# A-14732-40023-REPRODUCTION.net
KiCad netlist of a schematic drawn in EAGLE
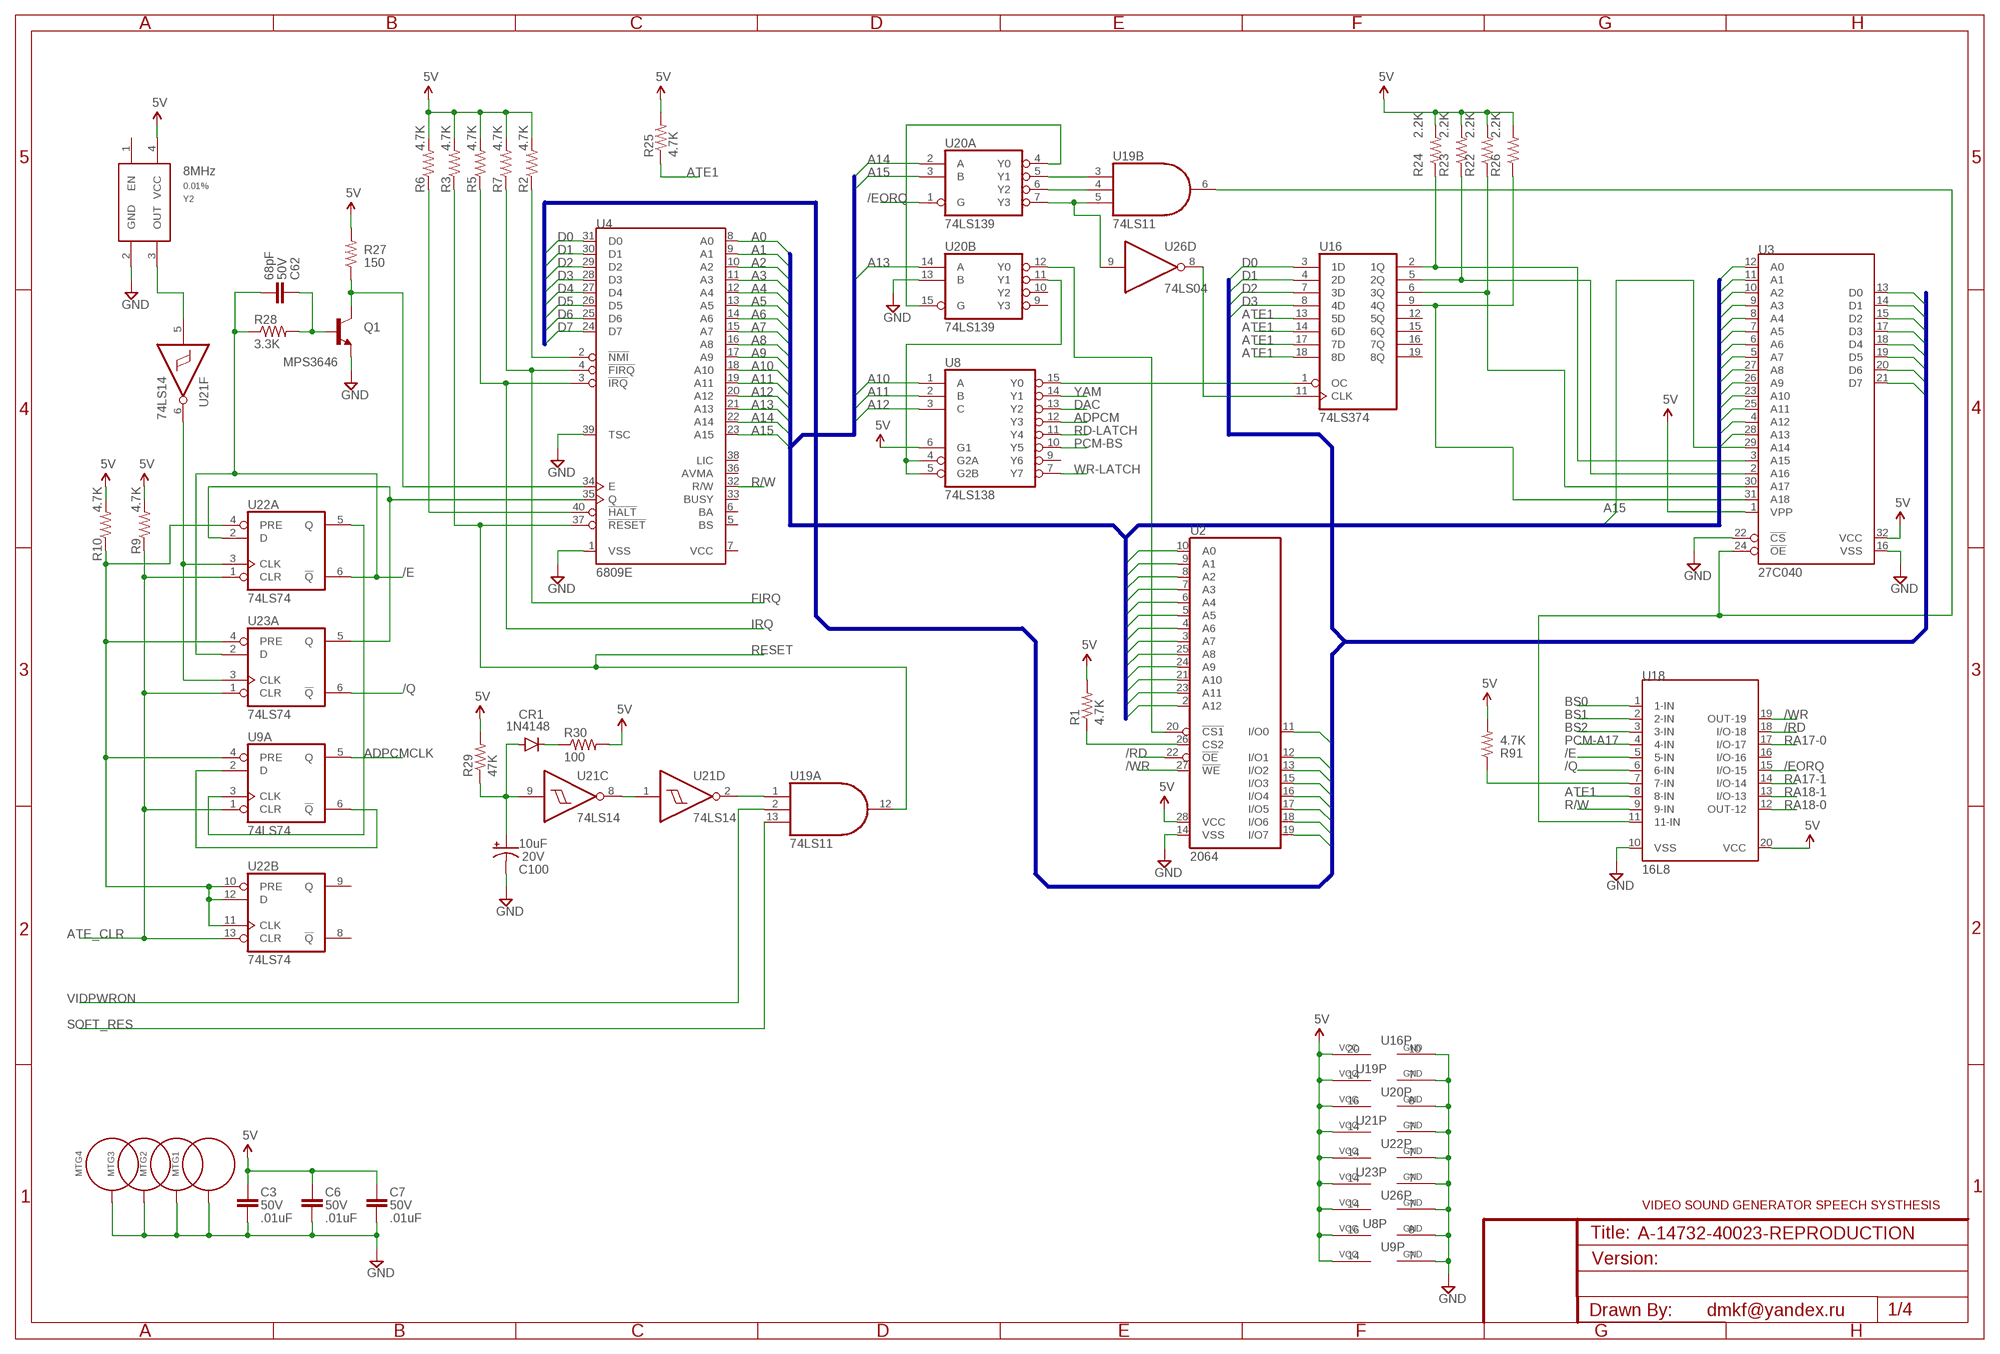
[diagram p0: schematic, sheet 1]
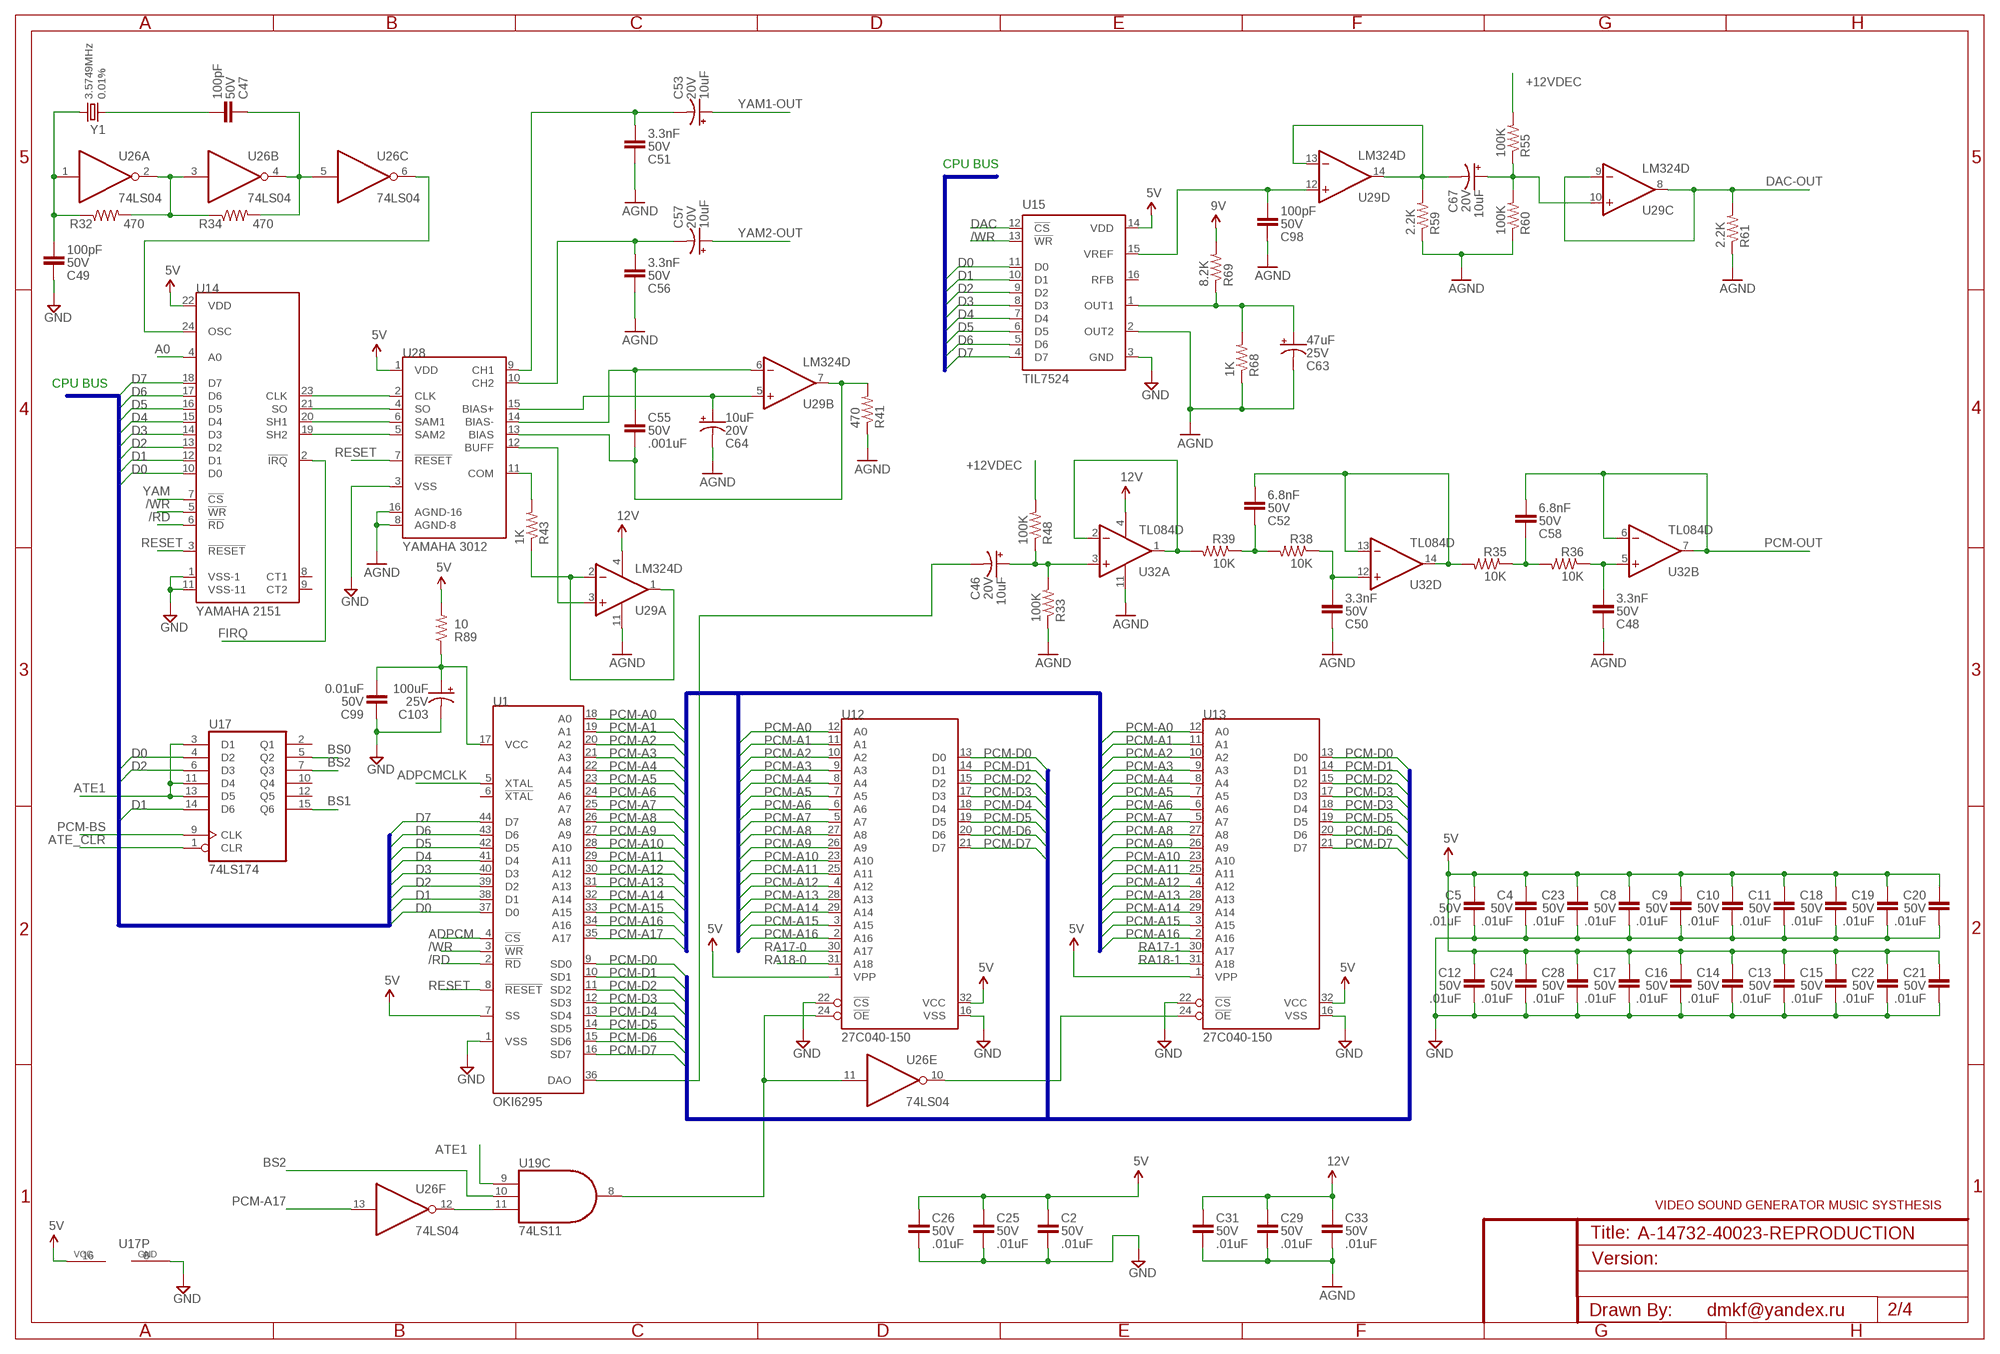
[diagram p1: schematic, sheet 2]
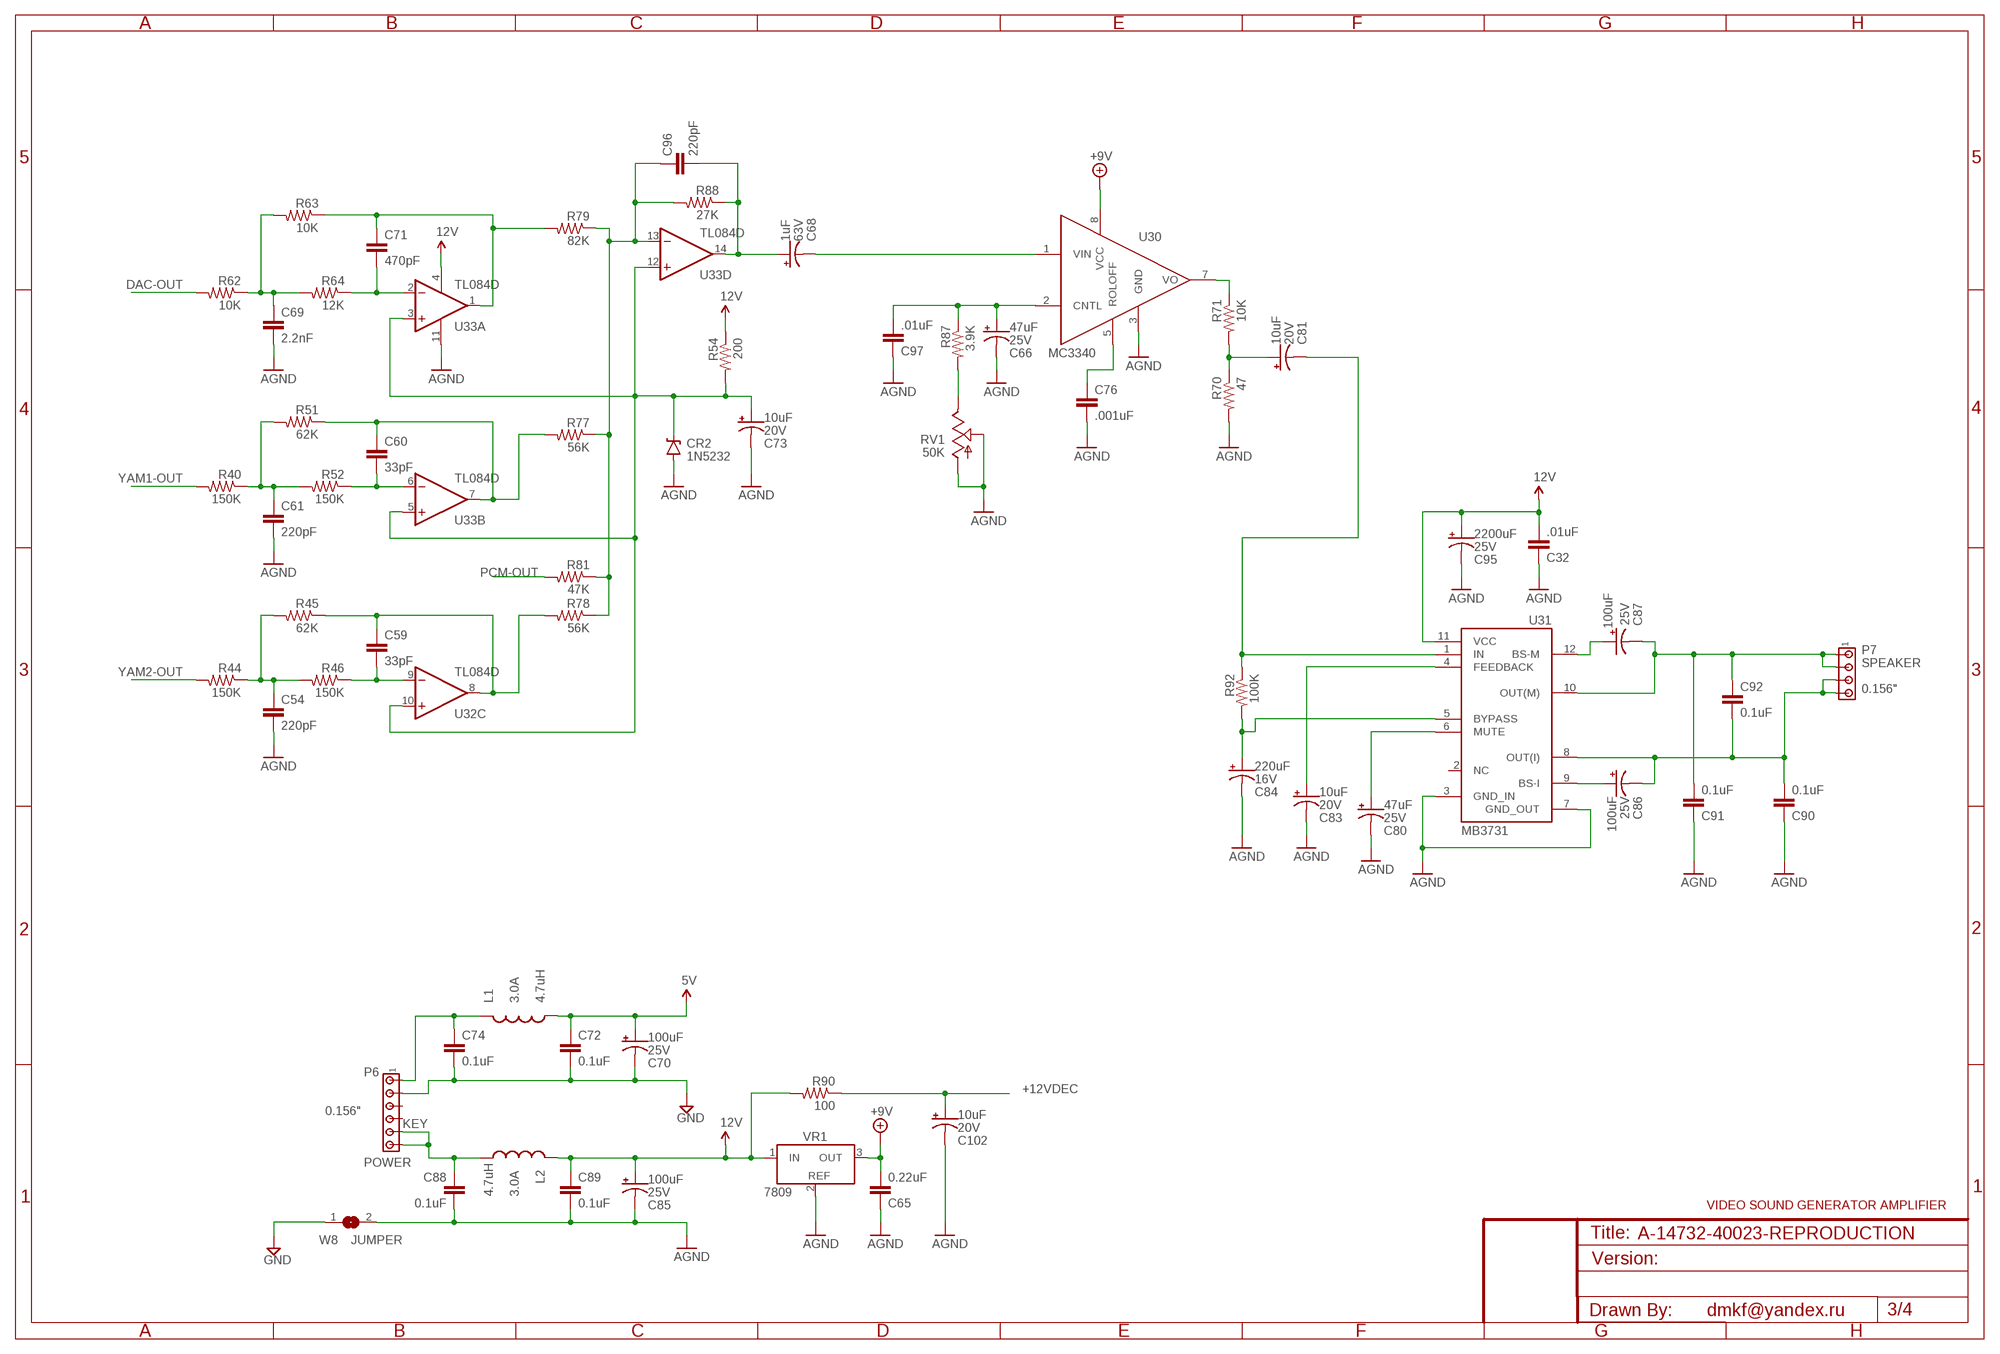
[diagram p2: schematic, sheet 3]
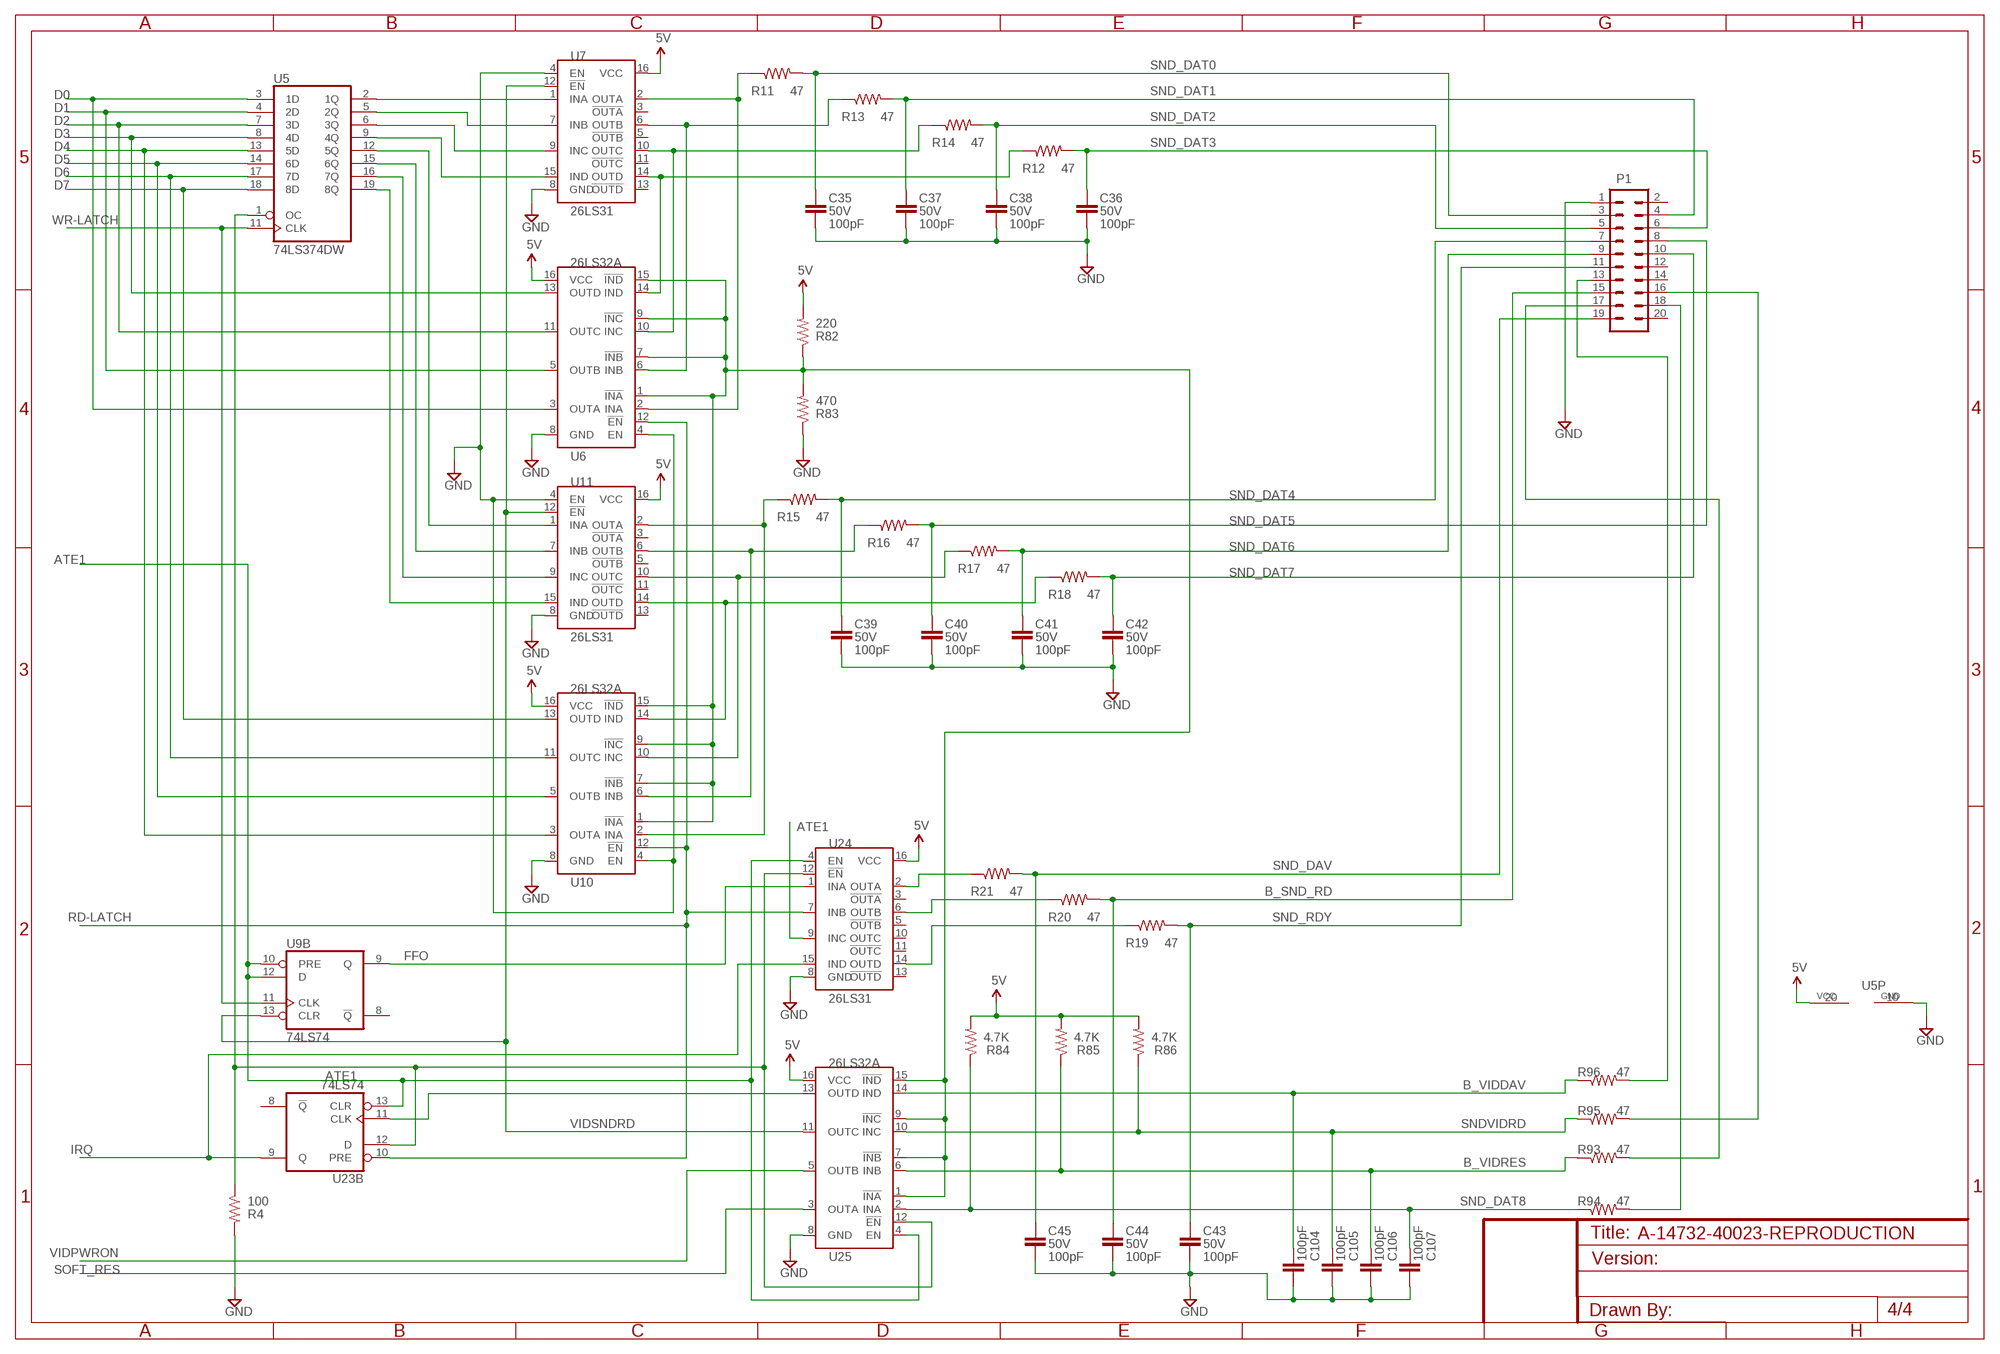
[diagram p3: schematic, sheet 4]

(export (version "E")
  (design (tool "Eeschema 10.0.6"))
  (components
    (comp (ref "C2")
      (value ".01uF")
      (footprint "eagle-import:0805")
      (fields (field (name "VOLTAGE") "50V"))
      (libsource (lib "eagle-import") (part "CAP0805"))
    )
    (comp (ref "C4")
      (value ".01uF")
      (footprint "eagle-import:0805")
      (fields (field (name "VOLTAGE") "50V"))
      (libsource (lib "eagle-import") (part "CAP0805"))
    )
    (comp (ref "C5")
      (value ".01uF")
      (footprint "eagle-import:0805")
      (fields (field (name "VOLTAGE") "50V"))
      (libsource (lib "eagle-import") (part "CAP0805"))
    )
    (comp (ref "C8")
      (value ".01uF")
      (footprint "eagle-import:0805")
      (fields (field (name "VOLTAGE") "50V"))
      (libsource (lib "eagle-import") (part "CAP0805"))
    )
    (comp (ref "C9")
      (value ".01uF")
      (footprint "eagle-import:0805")
      (fields (field (name "VOLTAGE") "50V"))
      (libsource (lib "eagle-import") (part "CAP0805"))
    )
    (comp (ref "C10")
      (value ".01uF")
      (footprint "eagle-import:0805")
      (fields (field (name "VOLTAGE") "50V"))
      (libsource (lib "eagle-import") (part "CAP0805"))
    )
    (comp (ref "C11")
      (value ".01uF")
      (footprint "eagle-import:0805")
      (fields (field (name "VOLTAGE") "50V"))
      (libsource (lib "eagle-import") (part "CAP0805"))
    )
    (comp (ref "C12")
      (value ".01uF")
      (footprint "eagle-import:0805")
      (fields (field (name "VOLTAGE") "50V"))
      (libsource (lib "eagle-import") (part "CAP0805"))
    )
    (comp (ref "C13")
      (value ".01uF")
      (footprint "eagle-import:0805")
      (fields (field (name "VOLTAGE") "50V"))
      (libsource (lib "eagle-import") (part "CAP0805"))
    )
    (comp (ref "C14")
      (value ".01uF")
      (footprint "eagle-import:0805")
      (fields (field (name "VOLTAGE") "50V"))
      (libsource (lib "eagle-import") (part "CAP0805"))
    )
    (comp (ref "C15")
      (value ".01uF")
      (footprint "eagle-import:0805")
      (fields (field (name "VOLTAGE") "50V"))
      (libsource (lib "eagle-import") (part "CAP0805"))
    )
    (comp (ref "C16")
      (value ".01uF")
      (footprint "eagle-import:0805")
      (fields (field (name "VOLTAGE") "50V"))
      (libsource (lib "eagle-import") (part "CAP0805"))
    )
    (comp (ref "C17")
      (value ".01uF")
      (footprint "eagle-import:0805")
      (fields (field (name "VOLTAGE") "50V"))
      (libsource (lib "eagle-import") (part "CAP0805"))
    )
    (comp (ref "C18")
      (value ".01uF")
      (footprint "eagle-import:0805")
      (fields (field (name "VOLTAGE") "50V"))
      (libsource (lib "eagle-import") (part "CAP0805"))
    )
    (comp (ref "C19")
      (value ".01uF")
      (footprint "eagle-import:0805")
      (fields (field (name "VOLTAGE") "50V"))
      (libsource (lib "eagle-import") (part "CAP0805"))
    )
    (comp (ref "C20")
      (value ".01uF")
      (footprint "eagle-import:0805")
      (fields (field (name "VOLTAGE") "50V"))
      (libsource (lib "eagle-import") (part "CAP0805"))
    )
    (comp (ref "C21")
      (value ".01uF")
      (footprint "eagle-import:0805")
      (fields (field (name "VOLTAGE") "50V"))
      (libsource (lib "eagle-import") (part "CAP0805"))
    )
    (comp (ref "C22")
      (value ".01uF")
      (footprint "eagle-import:0805")
      (fields (field (name "VOLTAGE") "50V"))
      (libsource (lib "eagle-import") (part "CAP0805"))
    )
    (comp (ref "C23")
      (value ".01uF")
      (footprint "eagle-import:0805")
      (fields (field (name "VOLTAGE") "50V"))
      (libsource (lib "eagle-import") (part "CAP0805"))
    )
    (comp (ref "C24")
      (value ".01uF")
      (footprint "eagle-import:0805")
      (fields (field (name "VOLTAGE") "50V"))
      (libsource (lib "eagle-import") (part "CAP0805"))
    )
    (comp (ref "C25")
      (value ".01uF")
      (footprint "eagle-import:0805")
      (fields (field (name "VOLTAGE") "50V"))
      (libsource (lib "eagle-import") (part "CAP0805"))
    )
    (comp (ref "C26")
      (value ".01uF")
      (footprint "eagle-import:0805")
      (fields (field (name "VOLTAGE") "50V"))
      (libsource (lib "eagle-import") (part "CAP0805"))
    )
    (comp (ref "C28")
      (value ".01uF")
      (footprint "eagle-import:0805")
      (fields (field (name "VOLTAGE") "50V"))
      (libsource (lib "eagle-import") (part "CAP0805"))
    )
    (comp (ref "C29")
      (value ".01uF")
      (footprint "eagle-import:0805")
      (fields (field (name "VOLTAGE") "50V"))
      (libsource (lib "eagle-import") (part "CAP0805"))
    )
    (comp (ref "C31")
      (value ".01uF")
      (footprint "eagle-import:0805")
      (fields (field (name "VOLTAGE") "50V"))
      (libsource (lib "eagle-import") (part "CAP0805"))
    )
    (comp (ref "C33")
      (value ".01uF")
      (footprint "eagle-import:0805")
      (fields (field (name "VOLTAGE") "50V"))
      (libsource (lib "eagle-import") (part "CAP0805"))
    )
    (comp (ref "C46")
      (value "10uF")
      (footprint "eagle-import:PANASONIC_C")
      (fields (field (name "VOLTAGE") "20V"))
      (libsource (lib "eagle-import") (part "CAP_POLC"))
    )
    (comp (ref "C47")
      (value "100pF")
      (footprint "eagle-import:0805")
      (fields (field (name "VOLTAGE") "50V"))
      (libsource (lib "eagle-import") (part "CAP0805"))
    )
    (comp (ref "C48")
      (value "3.3nF")
      (footprint "eagle-import:0805")
      (fields (field (name "VOLTAGE") "50V"))
      (libsource (lib "eagle-import") (part "CAP0805"))
    )
    (comp (ref "C49")
      (value "100pF")
      (footprint "eagle-import:0805")
      (fields (field (name "VOLTAGE") "50V"))
      (libsource (lib "eagle-import") (part "CAP0805"))
    )
    (comp (ref "C50")
      (value "3.3nF")
      (footprint "eagle-import:0805")
      (fields (field (name "VOLTAGE") "50V"))
      (libsource (lib "eagle-import") (part "CAP0805"))
    )
    (comp (ref "C51")
      (value "3.3nF")
      (footprint "eagle-import:0805")
      (fields (field (name "VOLTAGE") "50V"))
      (libsource (lib "eagle-import") (part "CAP0805"))
    )
    (comp (ref "C52")
      (value "6.8nF")
      (footprint "eagle-import:0805")
      (fields (field (name "VOLTAGE") "50V"))
      (libsource (lib "eagle-import") (part "CAP0805"))
    )
    (comp (ref "C53")
      (value "10uF")
      (footprint "eagle-import:PANASONIC_C")
      (fields (field (name "VOLTAGE") "20V"))
      (libsource (lib "eagle-import") (part "CAP_POLC"))
    )
    (comp (ref "C55")
      (value ".001uF")
      (footprint "eagle-import:0805")
      (fields (field (name "VOLTAGE") "50V"))
      (libsource (lib "eagle-import") (part "CAP0805"))
    )
    (comp (ref "C56")
      (value "3.3nF")
      (footprint "eagle-import:0805")
      (fields (field (name "VOLTAGE") "50V"))
      (libsource (lib "eagle-import") (part "CAP0805"))
    )
    (comp (ref "C57")
      (value "10uF")
      (footprint "eagle-import:PANASONIC_C")
      (fields (field (name "VOLTAGE") "20V"))
      (libsource (lib "eagle-import") (part "CAP_POLC"))
    )
    (comp (ref "C58")
      (value "6.8nF")
      (footprint "eagle-import:0805")
      (fields (field (name "VOLTAGE") "50V"))
      (libsource (lib "eagle-import") (part "CAP0805"))
    )
    (comp (ref "C63")
      (value "47uF")
      (footprint "eagle-import:PANASONIC_D")
      (fields (field (name "VOLTAGE") "25V"))
      (libsource (lib "eagle-import") (part "CAP_POLD"))
    )
    (comp (ref "C64")
      (value "10uF")
      (footprint "eagle-import:PANASONIC_C")
      (fields (field (name "VOLTAGE") "20V"))
      (libsource (lib "eagle-import") (part "CAP_POLC"))
    )
    (comp (ref "C67")
      (value "10uF")
      (footprint "eagle-import:PANASONIC_C")
      (fields (field (name "VOLTAGE") "20V"))
      (libsource (lib "eagle-import") (part "CAP_POLC"))
    )
    (comp (ref "C98")
      (value "100pF")
      (footprint "eagle-import:0805")
      (fields (field (name "VOLTAGE") "50V"))
      (libsource (lib "eagle-import") (part "CAP0805"))
    )
    (comp (ref "C99")
      (value "0.01uF")
      (footprint "eagle-import:0805")
      (fields (field (name "VOLTAGE") "50V"))
      (libsource (lib "eagle-import") (part "CAP0805"))
    )
    (comp (ref "C103")
      (value "100uF")
      (footprint "eagle-import:PANASONIC_D")
      (fields (field (name "VOLTAGE") "25V"))
      (libsource (lib "eagle-import") (part "CAP_POLD"))
    )
    (comp (ref "R32")
      (value "470")
      (footprint "eagle-import:0805")
      (libsource (lib "eagle-import") (part "RESISTOR0805-RES"))
    )
    (comp (ref "R33")
      (value "100K")
      (footprint "eagle-import:0805")
      (libsource (lib "eagle-import") (part "RESISTOR0805-RES"))
    )
    (comp (ref "R34")
      (value "470")
      (footprint "eagle-import:0805")
      (libsource (lib "eagle-import") (part "RESISTOR0805-RES"))
    )
    (comp (ref "R35")
      (value "10K")
      (footprint "eagle-import:0805")
      (libsource (lib "eagle-import") (part "RESISTOR0805-RES"))
    )
    (comp (ref "R36")
      (value "10K")
      (footprint "eagle-import:0805")
      (libsource (lib "eagle-import") (part "RESISTOR0805-RES"))
    )
    (comp (ref "R38")
      (value "10K")
      (footprint "eagle-import:0805")
      (libsource (lib "eagle-import") (part "RESISTOR0805-RES"))
    )
    (comp (ref "R39")
      (value "10K")
      (footprint "eagle-import:0805")
      (libsource (lib "eagle-import") (part "RESISTOR0805-RES"))
    )
    (comp (ref "R41")
      (value "470")
      (footprint "eagle-import:0805")
      (libsource (lib "eagle-import") (part "RESISTOR0805-RES"))
    )
    (comp (ref "R43")
      (value "1K")
      (footprint "eagle-import:0805")
      (libsource (lib "eagle-import") (part "RESISTOR0805-RES"))
    )
    (comp (ref "R48")
      (value "100K")
      (footprint "eagle-import:0805")
      (libsource (lib "eagle-import") (part "RESISTOR0805-RES"))
    )
    (comp (ref "R55")
      (value "100K")
      (footprint "eagle-import:0805")
      (libsource (lib "eagle-import") (part "RESISTOR0805-RES"))
    )
    (comp (ref "R59")
      (value "2.2K")
      (footprint "eagle-import:0805")
      (libsource (lib "eagle-import") (part "RESISTOR0805-RES"))
    )
    (comp (ref "R60")
      (value "100K")
      (footprint "eagle-import:0805")
      (libsource (lib "eagle-import") (part "RESISTOR0805-RES"))
    )
    (comp (ref "R61")
      (value "2.2K")
      (footprint "eagle-import:0805")
      (libsource (lib "eagle-import") (part "RESISTOR0805-RES"))
    )
    (comp (ref "R68")
      (value "1K")
      (footprint "eagle-import:0805")
      (libsource (lib "eagle-import") (part "RESISTOR0805-RES"))
    )
    (comp (ref "R69")
      (value "8.2K")
      (footprint "eagle-import:0805")
      (libsource (lib "eagle-import") (part "RESISTOR0805-RES"))
    )
    (comp (ref "R89")
      (value "10")
      (footprint "eagle-import:1206")
      (libsource (lib "eagle-import") (part "RESISTOR1206"))
    )
    (comp (ref "U1")
      (value "OKI6295")
      (footprint "eagle-import:QFP44")
      (libsource (lib "eagle-import") (part "OKI6295"))
    )
    (comp (ref "U12")
      (value "27C040-150")
      (footprint "eagle-import:PLCC32R")
      (libsource (lib "eagle-import") (part "27C040PLCC32"))
    )
    (comp (ref "U13")
      (value "27C040-150")
      (footprint "eagle-import:PLCC32R")
      (libsource (lib "eagle-import") (part "27C040PLCC32"))
    )
    (comp (ref "U14")
      (value "YAMAHA 2151")
      (footprint "eagle-import:DIP24")
      (libsource (lib "eagle-import") (part "YM2151"))
    )
    (comp (ref "U15")
      (value "TIL7524")
      (footprint "eagle-import:SOIC16N")
      (fields (field (name "MF") "ALTERA CORPORATION") (field (name "MPN") "AD7524JRZ"))
      (libsource (lib "eagle-import") (part "AD7524RJ"))
    )
    (comp (ref "U17")
      (value "74LS174")
      (footprint "eagle-import:SO16")
      (libsource (lib "eagle-import") (part "74174DLS"))
    )
    (comp (ref "U19")
      (value "74LS11")
      (footprint "eagle-import:SO14")
      (libsource (lib "eagle-import") (part "7411DLS"))
    )
    (comp (ref "U26")
      (value "74LS04")
      (footprint "eagle-import:SO14")
      (libsource (lib "eagle-import") (part "7404DLS"))
    )
    (comp (ref "U28")
      (value "YAMAHA 3012")
      (footprint "eagle-import:DIP16N")
      (libsource (lib "eagle-import") (part "YM3012"))
    )
    (comp (ref "U29")
      (value "LM324D")
      (footprint "eagle-import:SO14")
      (libsource (lib "eagle-import") (part "LM324D"))
    )
    (comp (ref "U32")
      (value "TL084D")
      (footprint "eagle-import:SO14")
      (libsource (lib "eagle-import") (part "TL084D"))
    )
    (comp (ref "Y1")
      (value "3.5749MHz")
      (footprint "eagle-import:HC49UP")
      (fields (field (name "TOLERANCE") "0.01%"))
      (libsource (lib "eagle-import") (part "CRYSTALHC49UP"))
    )
    (comp (ref "C32")
      (value ".01uF")
      (footprint "eagle-import:0805")
      (fields (field (name "VOLTAGE") "50V"))
      (libsource (lib "eagle-import") (part "CAP0805"))
    )
    (comp (ref "C54")
      (value "220pF")
      (footprint "eagle-import:0805")
      (fields (field (name "VOLTAGE") "50V"))
      (libsource (lib "eagle-import") (part "CAP0805"))
    )
    (comp (ref "C59")
      (value "33pF")
      (footprint "eagle-import:0805")
      (fields (field (name "VOLTAGE") "50V"))
      (libsource (lib "eagle-import") (part "CAP0805"))
    )
    (comp (ref "C60")
      (value "33pF")
      (footprint "eagle-import:0805")
      (fields (field (name "VOLTAGE") "50V"))
      (libsource (lib "eagle-import") (part "CAP0805"))
    )
    (comp (ref "C61")
      (value "220pF")
      (footprint "eagle-import:0805")
      (fields (field (name "VOLTAGE") "50V"))
      (libsource (lib "eagle-import") (part "CAP0805"))
    )
    (comp (ref "C65")
      (value "0.22uF")
      (footprint "eagle-import:0805")
      (fields (field (name "VOLTAGE") "50V"))
      (libsource (lib "eagle-import") (part "CAP0805"))
    )
    (comp (ref "C66")
      (value "47uF")
      (footprint "eagle-import:PANASONIC_D")
      (fields (field (name "VOLTAGE") "25V"))
      (libsource (lib "eagle-import") (part "CAP_POLD"))
    )
    (comp (ref "C68")
      (value "1uF")
      (footprint "eagle-import:PANASONIC_C")
      (fields (field (name "VOLTAGE") "63V"))
      (libsource (lib "eagle-import") (part "CAP_POLC"))
    )
    (comp (ref "C69")
      (value "2.2nF")
      (footprint "eagle-import:0805")
      (fields (field (name "VOLTAGE") "50V"))
      (libsource (lib "eagle-import") (part "CAP0805"))
    )
    (comp (ref "C70")
      (value "100uF")
      (footprint "eagle-import:PANASONIC_D")
      (fields (field (name "VOLTAGE") "25V"))
      (libsource (lib "eagle-import") (part "CAP_POLD"))
    )
    (comp (ref "C71")
      (value "470pF")
      (footprint "eagle-import:0805")
      (fields (field (name "VOLTAGE") "50V"))
      (libsource (lib "eagle-import") (part "CAP0805"))
    )
    (comp (ref "C72")
      (value "0.1uF")
      (footprint "eagle-import:0805")
      (fields (field (name "VOLTAGE") "50V"))
      (libsource (lib "eagle-import") (part "CAP0805"))
    )
    (comp (ref "C73")
      (value "10uF")
      (footprint "eagle-import:PANASONIC_C")
      (fields (field (name "VOLTAGE") "20V"))
      (libsource (lib "eagle-import") (part "CAP_POLC"))
    )
    (comp (ref "C74")
      (value "0.1uF")
      (footprint "eagle-import:0805")
      (fields (field (name "VOLTAGE") "50V"))
      (libsource (lib "eagle-import") (part "CAP0805"))
    )
    (comp (ref "C76")
      (value ".001uF")
      (footprint "eagle-import:0805")
      (fields (field (name "VOLTAGE") "50V"))
      (libsource (lib "eagle-import") (part "CAP0805"))
    )
    (comp (ref "C80")
      (value "47uF")
      (footprint "eagle-import:PANASONIC_D")
      (fields (field (name "VOLTAGE") "25V"))
      (libsource (lib "eagle-import") (part "CAP_POLD"))
    )
    (comp (ref "C81")
      (value "10uF")
      (footprint "eagle-import:PANASONIC_C")
      (fields (field (name "VOLTAGE") "20V"))
      (libsource (lib "eagle-import") (part "CAP_POLC"))
    )
    (comp (ref "C83")
      (value "10uF")
      (footprint "eagle-import:PANASONIC_C")
      (fields (field (name "VOLTAGE") "20V"))
      (libsource (lib "eagle-import") (part "CAP_POLC"))
    )
    (comp (ref "C84")
      (value "220uF")
      (footprint "eagle-import:PANASONIC_E")
      (fields (field (name "VOLTAGE") "16V"))
      (libsource (lib "eagle-import") (part "CAP_POLE"))
    )
    (comp (ref "C85")
      (value "100uF")
      (footprint "eagle-import:PANASONIC_D")
      (fields (field (name "VOLTAGE") "25V"))
      (libsource (lib "eagle-import") (part "CAP_POLD"))
    )
    (comp (ref "C86")
      (value "100uF")
      (footprint "eagle-import:PANASONIC_D")
      (fields (field (name "VOLTAGE") "25V"))
      (libsource (lib "eagle-import") (part "CAP_POLD"))
    )
    (comp (ref "C87")
      (value "100uF")
      (footprint "eagle-import:PANASONIC_D")
      (fields (field (name "VOLTAGE") "25V"))
      (libsource (lib "eagle-import") (part "CAP_POLD"))
    )
    (comp (ref "C88")
      (value "0.1uF")
      (footprint "eagle-import:0805")
      (fields (field (name "VOLTAGE") "50V"))
      (libsource (lib "eagle-import") (part "CAP0805"))
    )
    (comp (ref "C89")
      (value "0.1uF")
      (footprint "eagle-import:0805")
      (fields (field (name "VOLTAGE") "50V"))
      (libsource (lib "eagle-import") (part "CAP0805"))
    )
    (comp (ref "C90")
      (value "0.1uF")
      (footprint "eagle-import:0805")
      (fields (field (name "VOLTAGE") "50V"))
      (libsource (lib "eagle-import") (part "CAP0805"))
    )
    (comp (ref "C91")
      (value "0.1uF")
      (footprint "eagle-import:0805")
      (fields (field (name "VOLTAGE") "50V"))
      (libsource (lib "eagle-import") (part "CAP0805"))
    )
    (comp (ref "C92")
      (value "0.1uF")
      (footprint "eagle-import:0805")
      (fields (field (name "VOLTAGE") "50V"))
      (libsource (lib "eagle-import") (part "CAP0805"))
    )
    (comp (ref "C95")
      (value "2200uF")
      (footprint "eagle-import:CPOL-RADIAL-1000UF-25V")
      (fields (field (name "VOLTAGE") "25V"))
      (libsource (lib "eagle-import") (part "CAP_POLPTH4"))
    )
    (comp (ref "C96")
      (value "220pF")
      (footprint "eagle-import:0805")
      (fields (field (name "VOLTAGE") "50V"))
      (libsource (lib "eagle-import") (part "CAP0805"))
    )
    (comp (ref "C97")
      (value ".01uF")
      (footprint "eagle-import:0805")
      (fields (field (name "VOLTAGE") "50V"))
      (libsource (lib "eagle-import") (part "CAP0805"))
    )
    (comp (ref "C102")
      (value "10uF")
      (footprint "eagle-import:PANASONIC_C")
      (fields (field (name "VOLTAGE") "20V"))
      (libsource (lib "eagle-import") (part "CAP_POLC"))
    )
    (comp (ref "CR2")
      (value "1N5232")
      (footprint "eagle-import:SOT23")
      (libsource (lib "eagle-import") (part "1N5232"))
    )
    (comp (ref "L1")
      (value "4.7uH")
      (footprint "eagle-import:NPI75C")
      (fields (field (name "CUR") "3.0A"))
      (libsource (lib "eagle-import") (part "INDUCTORNPI75"))
    )
    (comp (ref "L2")
      (value "4.7uH")
      (footprint "eagle-import:NPI75C")
      (fields (field (name "CURRENT") "3.0A"))
      (libsource (lib "eagle-import") (part "INDUCTORNPI75"))
    )
    (comp (ref "P6")
      (value "POWER")
      (footprint "eagle-import:1X6MTA")
      (fields (field (name "PITCH") "0.156\""))
      (libsource (lib "eagle-import") (part "MTA06-156"))
    )
    (comp (ref "P7")
      (value "SPEAKER")
      (footprint "eagle-import:1X4MTA")
      (fields (field (name "PITCH") "0.156\""))
      (libsource (lib "eagle-import") (part "MTA04-156"))
    )
    (comp (ref "R40")
      (value "150K")
      (footprint "eagle-import:0805")
      (libsource (lib "eagle-import") (part "RESISTOR0805-RES"))
    )
    (comp (ref "R44")
      (value "150K")
      (footprint "eagle-import:0805")
      (libsource (lib "eagle-import") (part "RESISTOR0805-RES"))
    )
    (comp (ref "R45")
      (value "62K")
      (footprint "eagle-import:0805")
      (libsource (lib "eagle-import") (part "RESISTOR0805-RES"))
    )
    (comp (ref "R46")
      (value "150K")
      (footprint "eagle-import:0805")
      (libsource (lib "eagle-import") (part "RESISTOR0805-RES"))
    )
    (comp (ref "R51")
      (value "62K")
      (footprint "eagle-import:0805")
      (libsource (lib "eagle-import") (part "RESISTOR0805-RES"))
    )
    (comp (ref "R52")
      (value "150K")
      (footprint "eagle-import:0805")
      (libsource (lib "eagle-import") (part "RESISTOR0805-RES"))
    )
    (comp (ref "R54")
      (value "200")
      (footprint "eagle-import:R1206")
      (libsource (lib "eagle-import") (part "R-US_R1206"))
    )
    (comp (ref "R62")
      (value "10K")
      (footprint "eagle-import:0805")
      (libsource (lib "eagle-import") (part "RESISTOR0805-RES"))
    )
    (comp (ref "R63")
      (value "10K")
      (footprint "eagle-import:0805")
      (libsource (lib "eagle-import") (part "RESISTOR0805-RES"))
    )
    (comp (ref "R64")
      (value "12K")
      (footprint "eagle-import:0805")
      (libsource (lib "eagle-import") (part "RESISTOR0805-RES"))
    )
    (comp (ref "R70")
      (value "47")
      (footprint "eagle-import:R1206")
      (libsource (lib "eagle-import") (part "R-US_R1206"))
    )
    (comp (ref "R71")
      (value "10K")
      (footprint "eagle-import:0805")
      (libsource (lib "eagle-import") (part "RESISTOR0805-RES"))
    )
    (comp (ref "R77")
      (value "56K")
      (footprint "eagle-import:0805")
      (libsource (lib "eagle-import") (part "RESISTOR0805-RES"))
    )
    (comp (ref "R78")
      (value "56K")
      (footprint "eagle-import:0805")
      (libsource (lib "eagle-import") (part "RESISTOR0805-RES"))
    )
    (comp (ref "R79")
      (value "82K")
      (footprint "eagle-import:0805")
      (libsource (lib "eagle-import") (part "RESISTOR0805-RES"))
    )
    (comp (ref "R81")
      (value "47K")
      (footprint "eagle-import:0805")
      (libsource (lib "eagle-import") (part "RESISTOR0805-RES"))
    )
    (comp (ref "R87")
      (value "3.9K")
      (footprint "eagle-import:0805")
      (libsource (lib "eagle-import") (part "RESISTOR0805-RES"))
    )
    (comp (ref "R88")
      (value "27K")
      (footprint "eagle-import:0805")
      (libsource (lib "eagle-import") (part "RESISTOR0805-RES"))
    )
    (comp (ref "R90")
      (value "100")
      (footprint "eagle-import:R1206")
      (libsource (lib "eagle-import") (part "R-US_R1206"))
    )
    (comp (ref "R92")
      (value "100K")
      (footprint "eagle-import:0805")
      (libsource (lib "eagle-import") (part "RESISTOR0805-RES"))
    )
    (comp (ref "RV1")
      (value "50K")
      (footprint "eagle-import:POT_ALPHA_RV16AF-20")
      (libsource (lib "eagle-import") (part "POT-RV16AF-20"))
    )
    (comp (ref "U30")
      (value "MC3340")
      (footprint "eagle-import:MC3340")
      (libsource (lib "eagle-import") (part "MC3340"))
    )
    (comp (ref "U31")
      (value "MB3731")
      (footprint "eagle-import:SIP12")
      (libsource (lib "eagle-import") (part "MB3731"))
    )
    (comp (ref "U33")
      (value "TL084D")
      (footprint "eagle-import:SO14")
      (libsource (lib "eagle-import") (part "TL084D"))
    )
    (comp (ref "VR1")
      (value "7809")
      (footprint "eagle-import:7809-TO220V")
      (fields (field (name "PARTNUMBER") "5460-12743-00"))
      (libsource (lib "eagle-import") (part "7809TO220"))
    )
    (comp (ref "W8")
      (value "JUMPER")
      (footprint "eagle-import:SJ")
      (libsource (lib "eagle-import") (part "SJ"))
    )
    (comp (ref "C35")
      (value "100pF")
      (footprint "eagle-import:0805")
      (fields (field (name "VOLTAGE") "50V"))
      (libsource (lib "eagle-import") (part "CAP0805"))
    )
    (comp (ref "C36")
      (value "100pF")
      (footprint "eagle-import:0805")
      (fields (field (name "VOLTAGE") "50V"))
      (libsource (lib "eagle-import") (part "CAP0805"))
    )
    (comp (ref "C37")
      (value "100pF")
      (footprint "eagle-import:0805")
      (fields (field (name "VOLTAGE") "50V"))
      (libsource (lib "eagle-import") (part "CAP0805"))
    )
    (comp (ref "C38")
      (value "100pF")
      (footprint "eagle-import:0805")
      (fields (field (name "VOLTAGE") "50V"))
      (libsource (lib "eagle-import") (part "CAP0805"))
    )
    (comp (ref "C39")
      (value "100pF")
      (footprint "eagle-import:0805")
      (fields (field (name "VOLTAGE") "50V"))
      (libsource (lib "eagle-import") (part "CAP0805"))
    )
    (comp (ref "C40")
      (value "100pF")
      (footprint "eagle-import:0805")
      (fields (field (name "VOLTAGE") "50V"))
      (libsource (lib "eagle-import") (part "CAP0805"))
    )
    (comp (ref "C41")
      (value "100pF")
      (footprint "eagle-import:0805")
      (fields (field (name "VOLTAGE") "50V"))
      (libsource (lib "eagle-import") (part "CAP0805"))
    )
    (comp (ref "C42")
      (value "100pF")
      (footprint "eagle-import:0805")
      (fields (field (name "VOLTAGE") "50V"))
      (libsource (lib "eagle-import") (part "CAP0805"))
    )
    (comp (ref "C43")
      (value "100pF")
      (footprint "eagle-import:0805")
      (fields (field (name "VOLTAGE") "50V"))
      (libsource (lib "eagle-import") (part "CAP0805"))
    )
    (comp (ref "C44")
      (value "100pF")
      (footprint "eagle-import:0805")
      (fields (field (name "VOLTAGE") "50V"))
      (libsource (lib "eagle-import") (part "CAP0805"))
    )
    (comp (ref "C45")
      (value "100pF")
      (footprint "eagle-import:0805")
      (fields (field (name "VOLTAGE") "50V"))
      (libsource (lib "eagle-import") (part "CAP0805"))
    )
    (comp (ref "C104")
      (value "100pF")
      (footprint "eagle-import:0805")
      (fields (field (name "VOLTAGE") "50V"))
      (libsource (lib "eagle-import") (part "CAP0805"))
    )
    (comp (ref "C105")
      (value "100pF")
      (footprint "eagle-import:0805")
      (fields (field (name "VOLTAGE") "50V"))
      (libsource (lib "eagle-import") (part "CAP0805"))
    )
    (comp (ref "C106")
      (value "100pF")
      (footprint "eagle-import:0805")
      (fields (field (name "VOLTAGE") "50V"))
      (libsource (lib "eagle-import") (part "CAP0805"))
    )
    (comp (ref "C107")
      (value "100pF")
      (footprint "eagle-import:0805")
      (fields (field (name "VOLTAGE") "50V"))
      (libsource (lib "eagle-import") (part "CAP0805"))
    )
    (comp (ref "P1")
      (value "M10X2ROUND_NOSILK")
      (footprint "eagle-import:2X10_ROUND_NOSILK")
      (libsource (lib "eagle-import") (part "M10X2ROUND_NOSILK"))
    )
    (comp (ref "R4")
      (value "100")
      (footprint "eagle-import:0805")
      (libsource (lib "eagle-import") (part "RESISTOR0805-RES"))
    )
    (comp (ref "R11")
      (value "47")
      (footprint "eagle-import:0805")
      (libsource (lib "eagle-import") (part "RESISTOR0805-RES"))
    )
    (comp (ref "R12")
      (value "47")
      (footprint "eagle-import:0805")
      (libsource (lib "eagle-import") (part "RESISTOR0805-RES"))
    )
    (comp (ref "R13")
      (value "47")
      (footprint "eagle-import:0805")
      (libsource (lib "eagle-import") (part "RESISTOR0805-RES"))
    )
    (comp (ref "R14")
      (value "47")
      (footprint "eagle-import:0805")
      (libsource (lib "eagle-import") (part "RESISTOR0805-RES"))
    )
    (comp (ref "R15")
      (value "47")
      (footprint "eagle-import:0805")
      (libsource (lib "eagle-import") (part "RESISTOR0805-RES"))
    )
    (comp (ref "R16")
      (value "47")
      (footprint "eagle-import:0805")
      (libsource (lib "eagle-import") (part "RESISTOR0805-RES"))
    )
    (comp (ref "R17")
      (value "47")
      (footprint "eagle-import:0805")
      (libsource (lib "eagle-import") (part "RESISTOR0805-RES"))
    )
    (comp (ref "R18")
      (value "47")
      (footprint "eagle-import:0805")
      (libsource (lib "eagle-import") (part "RESISTOR0805-RES"))
    )
    (comp (ref "R19")
      (value "47")
      (footprint "eagle-import:0805")
      (libsource (lib "eagle-import") (part "RESISTOR0805-RES"))
    )
    (comp (ref "R20")
      (value "47")
      (footprint "eagle-import:0805")
      (libsource (lib "eagle-import") (part "RESISTOR0805-RES"))
    )
    (comp (ref "R21")
      (value "47")
      (footprint "eagle-import:0805")
      (libsource (lib "eagle-import") (part "RESISTOR0805-RES"))
    )
    (comp (ref "R82")
      (value "220")
      (footprint "eagle-import:R0805")
      (libsource (lib "eagle-import") (part "R-US_R0805"))
    )
    (comp (ref "R83")
      (value "470")
      (footprint "eagle-import:R0805")
      (libsource (lib "eagle-import") (part "R-US_R0805"))
    )
    (comp (ref "R84")
      (value "4.7K")
      (footprint "eagle-import:0805")
      (libsource (lib "eagle-import") (part "RESISTOR0805-RES"))
    )
    (comp (ref "R85")
      (value "4.7K")
      (footprint "eagle-import:0805")
      (libsource (lib "eagle-import") (part "RESISTOR0805-RES"))
    )
    (comp (ref "R86")
      (value "4.7K")
      (footprint "eagle-import:0805")
      (libsource (lib "eagle-import") (part "RESISTOR0805-RES"))
    )
    (comp (ref "R93")
      (value "47")
      (footprint "eagle-import:0805")
      (libsource (lib "eagle-import") (part "RESISTOR0805-RES"))
    )
    (comp (ref "R94")
      (value "47")
      (footprint "eagle-import:0805")
      (libsource (lib "eagle-import") (part "RESISTOR0805-RES"))
    )
    (comp (ref "R95")
      (value "47")
      (footprint "eagle-import:0805")
      (libsource (lib "eagle-import") (part "RESISTOR0805-RES"))
    )
    (comp (ref "R96")
      (value "47")
      (footprint "eagle-import:0805")
      (libsource (lib "eagle-import") (part "RESISTOR0805-RES"))
    )
    (comp (ref "U5")
      (value "74LS374DW")
      (footprint "eagle-import:SO20W")
      (libsource (lib "eagle-import") (part "74374DWLS"))
    )
    (comp (ref "U6")
      (value "26LS32A")
      (footprint "eagle-import:SO16")
      (libsource (lib "eagle-import") (part "26LS32A"))
    )
    (comp (ref "U7")
      (value "26LS31")
      (footprint "eagle-import:SO16")
      (libsource (lib "eagle-import") (part "26LS31"))
    )
    (comp (ref "U9")
      (value "74LS74")
      (footprint "eagle-import:SO14")
      (libsource (lib "eagle-import") (part "7474DLS"))
    )
    (comp (ref "U10")
      (value "26LS32A")
      (footprint "eagle-import:SO16")
      (libsource (lib "eagle-import") (part "26LS32A"))
    )
    (comp (ref "U11")
      (value "26LS31")
      (footprint "eagle-import:SO16")
      (libsource (lib "eagle-import") (part "26LS31"))
    )
    (comp (ref "U23")
      (value "74LS74")
      (footprint "eagle-import:SO14")
      (libsource (lib "eagle-import") (part "7474DLS"))
    )
    (comp (ref "U24")
      (value "26LS31")
      (footprint "eagle-import:SO16")
      (libsource (lib "eagle-import") (part "26LS31"))
    )
    (comp (ref "U25")
      (value "26LS32A")
      (footprint "eagle-import:SO16")
      (libsource (lib "eagle-import") (part "26LS32A"))
    )
    (comp (ref "C3")
      (value ".01uF")
      (footprint "eagle-import:0805")
      (fields (field (name "VOLTAGE") "50V"))
      (libsource (lib "eagle-import") (part "CAP0805"))
    )
    (comp (ref "C6")
      (value ".01uF")
      (footprint "eagle-import:0805")
      (fields (field (name "VOLTAGE") "50V"))
      (libsource (lib "eagle-import") (part "CAP0805"))
    )
    (comp (ref "C7")
      (value ".01uF")
      (footprint "eagle-import:0805")
      (fields (field (name "VOLTAGE") "50V"))
      (libsource (lib "eagle-import") (part "CAP0805"))
    )
    (comp (ref "C62")
      (value "68pF")
      (footprint "eagle-import:0805")
      (libsource (lib "eagle-import") (part "CAP0805"))
    )
    (comp (ref "C100")
      (value "10uF")
      (footprint "eagle-import:PANASONIC_C")
      (fields (field (name "VOLTAGE") "20V"))
      (libsource (lib "eagle-import") (part "CAP_POLC"))
    )
    (comp (ref "CR1")
      (value "1N4148")
      (footprint "eagle-import:SMA-DIODE")
      (libsource (lib "eagle-import") (part "DIODESMA"))
    )
    (comp (ref "MTG1")
      (value "MTGHOLE")
      (footprint "eagle-import:STANDOFF-ELECTRICAL")
      (libsource (lib "eagle-import") (part "STANDOFF_ELECTRICAL"))
    )
    (comp (ref "MTG2")
      (value "MTGHOLE")
      (footprint "eagle-import:STANDOFF-ELECTRICAL")
      (libsource (lib "eagle-import") (part "STANDOFF_ELECTRICAL"))
    )
    (comp (ref "MTG3")
      (value "MTGHOLE")
      (footprint "eagle-import:STANDOFF-ELECTRICAL")
      (libsource (lib "eagle-import") (part "STANDOFF_ELECTRICAL"))
    )
    (comp (ref "MTG4")
      (value "MTGHOLE")
      (footprint "eagle-import:STANDOFF-ELECTRICAL")
      (libsource (lib "eagle-import") (part "STANDOFF_ELECTRICAL"))
    )
    (comp (ref "Q1")
      (value "MPS3646")
      (footprint "eagle-import:SOT23-3")
      (libsource (lib "eagle-import") (part "TRANSISTOR_NPNMMBT2222A"))
    )
    (comp (ref "R1")
      (value "4.7K")
      (footprint "eagle-import:0805")
      (libsource (lib "eagle-import") (part "RESISTOR0805-RES"))
    )
    (comp (ref "R2")
      (value "4.7K")
      (footprint "eagle-import:0805")
      (libsource (lib "eagle-import") (part "RESISTOR0805-RES"))
    )
    (comp (ref "R3")
      (value "4.7K")
      (footprint "eagle-import:0805")
      (libsource (lib "eagle-import") (part "RESISTOR0805-RES"))
    )
    (comp (ref "R5")
      (value "4.7K")
      (footprint "eagle-import:0805")
      (libsource (lib "eagle-import") (part "RESISTOR0805-RES"))
    )
    (comp (ref "R6")
      (value "4.7K")
      (footprint "eagle-import:0805")
      (libsource (lib "eagle-import") (part "RESISTOR0805-RES"))
    )
    (comp (ref "R7")
      (value "4.7K")
      (footprint "eagle-import:0805")
      (libsource (lib "eagle-import") (part "RESISTOR0805-RES"))
    )
    (comp (ref "R9")
      (value "4.7K")
      (footprint "eagle-import:0805")
      (libsource (lib "eagle-import") (part "RESISTOR0805-RES"))
    )
    (comp (ref "R10")
      (value "4.7K")
      (footprint "eagle-import:0805")
      (libsource (lib "eagle-import") (part "RESISTOR0805-RES"))
    )
    (comp (ref "R22")
      (value "2.2K")
      (footprint "eagle-import:0805")
      (libsource (lib "eagle-import") (part "RESISTOR0805-RES"))
    )
    (comp (ref "R23")
      (value "2.2K")
      (footprint "eagle-import:0805")
      (libsource (lib "eagle-import") (part "RESISTOR0805-RES"))
    )
    (comp (ref "R24")
      (value "2.2K")
      (footprint "eagle-import:0805")
      (libsource (lib "eagle-import") (part "RESISTOR0805-RES"))
    )
    (comp (ref "R25")
      (value "4.7K")
      (footprint "eagle-import:0805")
      (libsource (lib "eagle-import") (part "RESISTOR0805-RES"))
    )
    (comp (ref "R26")
      (value "2.2K")
      (footprint "eagle-import:0805")
      (libsource (lib "eagle-import") (part "RESISTOR0805-RES"))
    )
    (comp (ref "R27")
      (value "150")
      (footprint "eagle-import:1206")
      (libsource (lib "eagle-import") (part "RESISTOR1206"))
    )
    (comp (ref "R28")
      (value "3.3K")
      (footprint "eagle-import:0805")
      (libsource (lib "eagle-import") (part "RESISTOR0805-RES"))
    )
    (comp (ref "R29")
      (value "47K")
      (footprint "eagle-import:0805")
      (libsource (lib "eagle-import") (part "RESISTOR0805-RES"))
    )
    (comp (ref "R30")
      (value "100")
      (footprint "eagle-import:1206")
      (libsource (lib "eagle-import") (part "RESISTOR1206"))
    )
    (comp (ref "R91")
      (value "4.7K")
      (footprint "eagle-import:0805")
      (libsource (lib "eagle-import") (part "RESISTOR0805-RES"))
    )
    (comp (ref "U2")
      (value "2064")
      (footprint "eagle-import:SOP28")
      (libsource (lib "eagle-import") (part "MS6264LSOP28"))
    )
    (comp (ref "U3")
      (value "27C040")
      (footprint "eagle-import:PLCC32R")
      (libsource (lib "eagle-import") (part "27C040PLCC32"))
    )
    (comp (ref "U4")
      (value "6809E")
      (footprint "eagle-import:DIP40")
      (libsource (lib "eagle-import") (part "6809E"))
    )
    (comp (ref "U8")
      (value "74LS138")
      (footprint "eagle-import:SO16")
      (libsource (lib "eagle-import") (part "74138DLS"))
    )
    (comp (ref "U16")
      (value "74LS374")
      (footprint "eagle-import:SO20W")
      (libsource (lib "eagle-import") (part "74374DWLS"))
    )
    (comp (ref "U18")
      (value "16L8")
      (footprint "eagle-import:DIP20N")
      (libsource (lib "eagle-import") (part "PAL16L8"))
    )
    (comp (ref "U20")
      (value "74LS139")
      (footprint "eagle-import:SO16")
      (libsource (lib "eagle-import") (part "74139DLS"))
    )
    (comp (ref "U21")
      (value "74LS14")
      (footprint "eagle-import:SO14")
      (libsource (lib "eagle-import") (part "7414DLS"))
    )
    (comp (ref "U22")
      (value "74LS74")
      (footprint "eagle-import:SO14")
      (libsource (lib "eagle-import") (part "7474DLS"))
    )
    (comp (ref "Y2")
      (value "8MHz")
      (footprint "eagle-import:CRYSTAL-OSC-SMD-5X3")
      (fields (field (name "TOLERANCE") "0.01%"))
      (libsource (lib "eagle-import") (part "OSCILLATOR5X3-PIN1-INDICATED"))
    )
  )
  (nets
    (net (code "1") (name "+9V") (class "Default")
      (node (ref "C65") (pin "2") (pinfunction "2_2") (pintype "passive"))
      (node (ref "U30") (pin "8") (pinfunction "VCC_8") (pintype "power_in"))
      (node (ref "VR1") (pin "3") (pinfunction "OUT_3") (pintype "passive"))
    )
    (net (code "2") (name "+12VDEC") (class "Default")
      (node (ref "C102") (pin "+") (pinfunction "+_+") (pintype "passive"))
      (node (ref "R48") (pin "2") (pinfunction "2_2") (pintype "passive"))
      (node (ref "R55") (pin "2") (pinfunction "2_2") (pintype "passive"))
      (node (ref "R90") (pin "1") (pinfunction "1_1") (pintype "passive"))
    )
    (net (code "3") (name "5V") (class "Default")
      (node (ref "C10") (pin "1") (pinfunction "1_1") (pintype "passive"))
      (node (ref "C11") (pin "1") (pinfunction "1_1") (pintype "passive"))
      (node (ref "C12") (pin "1") (pinfunction "1_1") (pintype "passive"))
      (node (ref "C13") (pin "1") (pinfunction "1_1") (pintype "passive"))
      (node (ref "C14") (pin "1") (pinfunction "1_1") (pintype "passive"))
      (node (ref "C15") (pin "1") (pinfunction "1_1") (pintype "passive"))
      (node (ref "C16") (pin "1") (pinfunction "1_1") (pintype "passive"))
      (node (ref "C17") (pin "1") (pinfunction "1_1") (pintype "passive"))
      (node (ref "C18") (pin "1") (pinfunction "1_1") (pintype "passive"))
      (node (ref "C19") (pin "1") (pinfunction "1_1") (pintype "passive"))
      (node (ref "C2") (pin "1") (pinfunction "1_1") (pintype "passive"))
      (node (ref "C20") (pin "1") (pinfunction "1_1") (pintype "passive"))
      (node (ref "C21") (pin "1") (pinfunction "1_1") (pintype "passive"))
      (node (ref "C22") (pin "1") (pinfunction "1_1") (pintype "passive"))
      (node (ref "C23") (pin "1") (pinfunction "1_1") (pintype "passive"))
      (node (ref "C24") (pin "1") (pinfunction "1_1") (pintype "passive"))
      (node (ref "C25") (pin "1") (pinfunction "1_1") (pintype "passive"))
      (node (ref "C26") (pin "1") (pinfunction "1_1") (pintype "passive"))
      (node (ref "C28") (pin "1") (pinfunction "1_1") (pintype "passive"))
      (node (ref "C3") (pin "1") (pinfunction "1_1") (pintype "passive"))
      (node (ref "C4") (pin "1") (pinfunction "1_1") (pintype "passive"))
      (node (ref "C5") (pin "1") (pinfunction "1_1") (pintype "passive"))
      (node (ref "C6") (pin "1") (pinfunction "1_1") (pintype "passive"))
      (node (ref "C7") (pin "1") (pinfunction "1_1") (pintype "passive"))
      (node (ref "C70") (pin "+") (pinfunction "+_+") (pintype "passive"))
      (node (ref "C72") (pin "1") (pinfunction "1_1") (pintype "passive"))
      (node (ref "C8") (pin "1") (pinfunction "1_1") (pintype "passive"))
      (node (ref "C9") (pin "1") (pinfunction "1_1") (pintype "passive"))
      (node (ref "L1") (pin "1") (pinfunction "1_1") (pintype "passive"))
      (node (ref "R1") (pin "2") (pinfunction "2_2") (pintype "passive"))
      (node (ref "R10") (pin "2") (pinfunction "2_2") (pintype "passive"))
      (node (ref "R2") (pin "2") (pinfunction "2_2") (pintype "passive"))
      (node (ref "R22") (pin "2") (pinfunction "2_2") (pintype "passive"))
      (node (ref "R23") (pin "2") (pinfunction "2_2") (pintype "passive"))
      (node (ref "R24") (pin "2") (pinfunction "2_2") (pintype "passive"))
      (node (ref "R25") (pin "2") (pinfunction "2_2") (pintype "passive"))
      (node (ref "R26") (pin "2") (pinfunction "2_2") (pintype "passive"))
      (node (ref "R27") (pin "2") (pinfunction "2_2") (pintype "passive"))
      (node (ref "R29") (pin "2") (pinfunction "2_2") (pintype "passive"))
      (node (ref "R3") (pin "2") (pinfunction "2_2") (pintype "passive"))
      (node (ref "R30") (pin "2") (pinfunction "2_2") (pintype "passive"))
      (node (ref "R5") (pin "2") (pinfunction "2_2") (pintype "passive"))
      (node (ref "R6") (pin "2") (pinfunction "2_2") (pintype "passive"))
      (node (ref "R69") (pin "2") (pinfunction "2_2") (pintype "passive"))
      (node (ref "R7") (pin "2") (pinfunction "2_2") (pintype "passive"))
      (node (ref "R82") (pin "2") (pinfunction "2_2") (pintype "passive"))
      (node (ref "R84") (pin "2") (pinfunction "2_2") (pintype "passive"))
      (node (ref "R85") (pin "2") (pinfunction "2_2") (pintype "passive"))
      (node (ref "R86") (pin "2") (pinfunction "2_2") (pintype "passive"))
      (node (ref "R89") (pin "2") (pinfunction "2_2") (pintype "passive"))
      (node (ref "R9") (pin "2") (pinfunction "2_2") (pintype "passive"))
      (node (ref "R91") (pin "2") (pinfunction "2_2") (pintype "passive"))
      (node (ref "U1") (pin "7") (pinfunction "SS_7") (pintype "passive"))
      (node (ref "U10") (pin "16") (pinfunction "VCC_16") (pintype "power_in"))
      (node (ref "U11") (pin "16") (pinfunction "VCC_16") (pintype "power_in"))
      (node (ref "U12") (pin "1") (pinfunction "VPP_1") (pintype "passive"))
      (node (ref "U12") (pin "32") (pinfunction "VCC_32") (pintype "passive"))
      (node (ref "U13") (pin "1") (pinfunction "VPP_1") (pintype "passive"))
      (node (ref "U13") (pin "32") (pinfunction "VCC_32") (pintype "passive"))
      (node (ref "U14") (pin "22") (pinfunction "VDD_22") (pintype "passive"))
      (node (ref "U15") (pin "14") (pinfunction "VDD_14") (pintype "power_in"))
      (node (ref "U16") (pin "20") (pinfunction "VCC_20") (pintype "power_in"))
      (node (ref "U17") (pin "16") (pinfunction "VCC_16") (pintype "power_in"))
      (node (ref "U18") (pin "20") (pinfunction "VCC_20") (pintype "passive"))
      (node (ref "U19") (pin "14") (pinfunction "VCC_14") (pintype "power_in"))
      (node (ref "U2") (pin "28") (pinfunction "VCC_28") (pintype "power_in"))
      (node (ref "U20") (pin "16") (pinfunction "VCC_16") (pintype "power_in"))
      (node (ref "U21") (pin "14") (pinfunction "VCC_14") (pintype "power_in"))
      (node (ref "U22") (pin "14") (pinfunction "VCC_14") (pintype "power_in"))
      (node (ref "U23") (pin "14") (pinfunction "VCC_14") (pintype "power_in"))
      (node (ref "U24") (pin "16") (pinfunction "VCC_16") (pintype "power_in"))
      (node (ref "U25") (pin "16") (pinfunction "VCC_16") (pintype "power_in"))
      (node (ref "U26") (pin "14") (pinfunction "VCC_14") (pintype "power_in"))
      (node (ref "U28") (pin "1") (pinfunction "VDD_1") (pintype "passive"))
      (node (ref "U3") (pin "1") (pinfunction "VPP_1") (pintype "passive"))
      (node (ref "U3") (pin "32") (pinfunction "VCC_32") (pintype "passive"))
      (node (ref "U5") (pin "20") (pinfunction "VCC_20") (pintype "power_in"))
      (node (ref "U6") (pin "16") (pinfunction "VCC_16") (pintype "power_in"))
      (node (ref "U7") (pin "16") (pinfunction "VCC_16") (pintype "power_in"))
      (node (ref "U8") (pin "16") (pinfunction "VCC_16") (pintype "power_in"))
      (node (ref "U8") (pin "6") (pinfunction "G1_6") (pintype "input"))
      (node (ref "U9") (pin "14") (pinfunction "VCC_14") (pintype "power_in"))
      (node (ref "Y2") (pin "4") (pinfunction "VCC_4") (pintype "bidirectional"))
    )
    (net (code "4") (name "12V") (class "Default")
      (node (ref "C29") (pin "1") (pinfunction "1_1") (pintype "passive"))
      (node (ref "C31") (pin "1") (pinfunction "1_1") (pintype "passive"))
      (node (ref "C32") (pin "2") (pinfunction "2_2") (pintype "passive"))
      (node (ref "C33") (pin "1") (pinfunction "1_1") (pintype "passive"))
      (node (ref "C85") (pin "+") (pinfunction "+_+") (pintype "passive"))
      (node (ref "C89") (pin "1") (pinfunction "1_1") (pintype "passive"))
      (node (ref "C95") (pin "1") (pinfunction "+_1") (pintype "passive"))
      (node (ref "L2") (pin "2") (pinfunction "2_2") (pintype "passive"))
      (node (ref "R54") (pin "1") (pinfunction "1_1") (pintype "passive"))
      (node (ref "R90") (pin "2") (pinfunction "2_2") (pintype "passive"))
      (node (ref "U29") (pin "4") (pinfunction "V+_4") (pintype "power_in"))
      (node (ref "U31") (pin "11") (pinfunction "VCC_11") (pintype "power_in"))
      (node (ref "U32") (pin "4") (pinfunction "V+_4") (pintype "power_in"))
      (node (ref "U33") (pin "4") (pinfunction "V+_4") (pintype "power_in"))
      (node (ref "VR1") (pin "1") (pinfunction "IN_1") (pintype "input"))
    )
    (net (code "5") (name "A0") (class "Default")
      (node (ref "U14") (pin "4") (pinfunction "A0_4") (pintype "passive"))
      (node (ref "U2") (pin "10") (pinfunction "A0_10") (pintype "input"))
      (node (ref "U3") (pin "12") (pinfunction "A0_12") (pintype "passive"))
      (node (ref "U4") (pin "8") (pinfunction "A0_8") (pintype "passive"))
    )
    (net (code "6") (name "A1") (class "Default")
      (node (ref "U2") (pin "9") (pinfunction "A1_9") (pintype "input"))
      (node (ref "U3") (pin "11") (pinfunction "A1_11") (pintype "passive"))
      (node (ref "U4") (pin "9") (pinfunction "A1_9") (pintype "passive"))
    )
    (net (code "7") (name "A2") (class "Default")
      (node (ref "U2") (pin "8") (pinfunction "A2_8") (pintype "input"))
      (node (ref "U3") (pin "10") (pinfunction "A2_10") (pintype "passive"))
      (node (ref "U4") (pin "10") (pinfunction "A2_10") (pintype "passive"))
    )
    (net (code "8") (name "A3") (class "Default")
      (node (ref "U2") (pin "7") (pinfunction "A3_7") (pintype "input"))
      (node (ref "U3") (pin "9") (pinfunction "A3_9") (pintype "passive"))
      (node (ref "U4") (pin "11") (pinfunction "A3_11") (pintype "passive"))
    )
    (net (code "9") (name "A4") (class "Default")
      (node (ref "U2") (pin "6") (pinfunction "A4_6") (pintype "input"))
      (node (ref "U3") (pin "8") (pinfunction "A4_8") (pintype "passive"))
      (node (ref "U4") (pin "12") (pinfunction "A4_12") (pintype "passive"))
    )
    (net (code "10") (name "A5") (class "Default")
      (node (ref "U2") (pin "5") (pinfunction "A5_5") (pintype "input"))
      (node (ref "U3") (pin "7") (pinfunction "A5_7") (pintype "passive"))
      (node (ref "U4") (pin "13") (pinfunction "A5_13") (pintype "passive"))
    )
    (net (code "11") (name "A6") (class "Default")
      (node (ref "U2") (pin "4") (pinfunction "A6_4") (pintype "input"))
      (node (ref "U3") (pin "6") (pinfunction "A6_6") (pintype "passive"))
      (node (ref "U4") (pin "14") (pinfunction "A6_14") (pintype "passive"))
    )
    (net (code "12") (name "A7") (class "Default")
      (node (ref "U2") (pin "3") (pinfunction "A7_3") (pintype "input"))
      (node (ref "U3") (pin "5") (pinfunction "A7_5") (pintype "passive"))
      (node (ref "U4") (pin "15") (pinfunction "A7_15") (pintype "passive"))
    )
    (net (code "13") (name "A8") (class "Default")
      (node (ref "U2") (pin "25") (pinfunction "A8_25") (pintype "input"))
      (node (ref "U3") (pin "27") (pinfunction "A8_27") (pintype "passive"))
      (node (ref "U4") (pin "16") (pinfunction "A8_16") (pintype "passive"))
    )
    (net (code "14") (name "A9") (class "Default")
      (node (ref "U2") (pin "24") (pinfunction "A9_24") (pintype "input"))
      (node (ref "U3") (pin "26") (pinfunction "A9_26") (pintype "passive"))
      (node (ref "U4") (pin "17") (pinfunction "A9_17") (pintype "passive"))
    )
    (net (code "15") (name "A10") (class "Default")
      (node (ref "U2") (pin "21") (pinfunction "A10_21") (pintype "input"))
      (node (ref "U3") (pin "23") (pinfunction "A10_23") (pintype "passive"))
      (node (ref "U4") (pin "18") (pinfunction "A10_18") (pintype "passive"))
      (node (ref "U8") (pin "1") (pinfunction "A_1") (pintype "input"))
    )
    (net (code "16") (name "A11") (class "Default")
      (node (ref "U2") (pin "23") (pinfunction "A11_23") (pintype "input"))
      (node (ref "U3") (pin "25") (pinfunction "A11_25") (pintype "passive"))
      (node (ref "U4") (pin "19") (pinfunction "A11_19") (pintype "passive"))
      (node (ref "U8") (pin "2") (pinfunction "B_2") (pintype "input"))
    )
    (net (code "17") (name "A12") (class "Default")
      (node (ref "U2") (pin "2") (pinfunction "A12_2") (pintype "input"))
      (node (ref "U3") (pin "4") (pinfunction "A12_4") (pintype "passive"))
      (node (ref "U4") (pin "20") (pinfunction "A12_20") (pintype "passive"))
      (node (ref "U8") (pin "3") (pinfunction "C_3") (pintype "input"))
    )
    (net (code "18") (name "A13") (class "Default")
      (node (ref "U20") (pin "14") (pinfunction "A_14") (pintype "input"))
      (node (ref "U3") (pin "28") (pinfunction "A13_28") (pintype "passive"))
      (node (ref "U4") (pin "21") (pinfunction "A13_21") (pintype "passive"))
    )
    (net (code "19") (name "A14") (class "Default")
      (node (ref "U20") (pin "2") (pinfunction "A_2") (pintype "input"))
      (node (ref "U4") (pin "22") (pinfunction "A14_22") (pintype "passive"))
    )
    (net (code "20") (name "A15") (class "Default")
      (node (ref "U20") (pin "3") (pinfunction "B_3") (pintype "input"))
      (node (ref "U3") (pin "29") (pinfunction "A14_29") (pintype "passive"))
      (node (ref "U4") (pin "23") (pinfunction "A15_23") (pintype "passive"))
    )
    (net (code "21") (name "ADPCM") (class "Default")
      (node (ref "U1") (pin "4") (pinfunction "~{CS}_4") (pintype "passive"))
      (node (ref "U8") (pin "12") (pinfunction "Y3_12") (pintype "output"))
    )
    (net (code "22") (name "ADPCMCLK") (class "Default")
      (node (ref "U1") (pin "5") (pinfunction "XTAL_5") (pintype "passive"))
      (node (ref "U9") (pin "5") (pinfunction "Q_5") (pintype "output"))
    )
    (net (code "23") (name "AGND") (class "Default")
      (node (ref "C102") (pin "-") (pinfunction "-_-") (pintype "passive"))
      (node (ref "C29") (pin "2") (pinfunction "2_2") (pintype "passive"))
      (node (ref "C31") (pin "2") (pinfunction "2_2") (pintype "passive"))
      (node (ref "C32") (pin "1") (pinfunction "1_1") (pintype "passive"))
      (node (ref "C33") (pin "2") (pinfunction "2_2") (pintype "passive"))
      (node (ref "C48") (pin "2") (pinfunction "2_2") (pintype "passive"))
      (node (ref "C50") (pin "2") (pinfunction "2_2") (pintype "passive"))
      (node (ref "C51") (pin "2") (pinfunction "2_2") (pintype "passive"))
      (node (ref "C54") (pin "2") (pinfunction "2_2") (pintype "passive"))
      (node (ref "C56") (pin "2") (pinfunction "2_2") (pintype "passive"))
      (node (ref "C61") (pin "2") (pinfunction "2_2") (pintype "passive"))
      (node (ref "C63") (pin "-") (pinfunction "-_-") (pintype "passive"))
      (node (ref "C64") (pin "-") (pinfunction "-_-") (pintype "passive"))
      (node (ref "C65") (pin "1") (pinfunction "1_1") (pintype "passive"))
      (node (ref "C66") (pin "-") (pinfunction "-_-") (pintype "passive"))
      (node (ref "C69") (pin "2") (pinfunction "2_2") (pintype "passive"))
      (node (ref "C73") (pin "-") (pinfunction "-_-") (pintype "passive"))
      (node (ref "C76") (pin "2") (pinfunction "2_2") (pintype "passive"))
      (node (ref "C80") (pin "-") (pinfunction "-_-") (pintype "passive"))
      (node (ref "C83") (pin "-") (pinfunction "-_-") (pintype "passive"))
      (node (ref "C84") (pin "-") (pinfunction "-_-") (pintype "passive"))
      (node (ref "C85") (pin "-") (pinfunction "-_-") (pintype "passive"))
      (node (ref "C88") (pin "2") (pinfunction "2_2") (pintype "passive"))
      (node (ref "C89") (pin "2") (pinfunction "2_2") (pintype "passive"))
      (node (ref "C90") (pin "1") (pinfunction "1_1") (pintype "passive"))
      (node (ref "C91") (pin "1") (pinfunction "1_1") (pintype "passive"))
      (node (ref "C95") (pin "2") (pinfunction "-_2") (pintype "passive"))
      (node (ref "C97") (pin "1") (pinfunction "1_1") (pintype "passive"))
      (node (ref "C98") (pin "2") (pinfunction "2_2") (pintype "passive"))
      (node (ref "CR2") (pin "1") (pinfunction "A_1") (pintype "passive"))
      (node (ref "R33") (pin "1") (pinfunction "1_1") (pintype "passive"))
      (node (ref "R41") (pin "1") (pinfunction "1_1") (pintype "passive"))
      (node (ref "R59") (pin "1") (pinfunction "1_1") (pintype "passive"))
      (node (ref "R60") (pin "1") (pinfunction "1_1") (pintype "passive"))
      (node (ref "R61") (pin "1") (pinfunction "1_1") (pintype "passive"))
      (node (ref "R68") (pin "1") (pinfunction "1_1") (pintype "passive"))
      (node (ref "R70") (pin "2") (pinfunction "2_2") (pintype "passive"))
      (node (ref "RV1") (pin "1") (pinfunction "A_1") (pintype "passive"))
      (node (ref "RV1") (pin "2") (pinfunction "S_2") (pintype "passive"))
      (node (ref "U15") (pin "2") (pinfunction "OUT2_2") (pintype "passive"))
      (node (ref "U28") (pin "16") (pinfunction "AGND-16_16") (pintype "passive"))
      (node (ref "U28") (pin "8") (pinfunction "AGND-8_8") (pintype "passive"))
      (node (ref "U29") (pin "11") (pinfunction "V-_11") (pintype "power_in"))
      (node (ref "U30") (pin "3") (pinfunction "GND_3") (pintype "power_in"))
      (node (ref "U31") (pin "3") (pinfunction "GND_IN_3") (pintype "power_in"))
      (node (ref "U31") (pin "7") (pinfunction "GND_OUT_7") (pintype "passive"))
      (node (ref "U32") (pin "11") (pinfunction "V-_11") (pintype "power_in"))
      (node (ref "U33") (pin "11") (pinfunction "V-_11") (pintype "power_in"))
      (node (ref "VR1") (pin "2") (pinfunction "REF_2") (pintype "passive"))
      (node (ref "W8") (pin "2") (pinfunction "2_2") (pintype "passive"))
    )
    (net (code "24") (name "ATE1") (class "Default")
      (node (ref "R25") (pin "1") (pinfunction "1_1") (pintype "passive"))
      (node (ref "U16") (pin "13") (pinfunction "5D_13") (pintype "input"))
      (node (ref "U16") (pin "14") (pinfunction "6D_14") (pintype "input"))
      (node (ref "U16") (pin "17") (pinfunction "7D_17") (pintype "input"))
      (node (ref "U16") (pin "18") (pinfunction "8D_18") (pintype "input"))
      (node (ref "U17") (pin "11") (pinfunction "D4_11") (pintype "input"))
      (node (ref "U17") (pin "13") (pinfunction "D5_13") (pintype "input"))
      (node (ref "U17") (pin "3") (pinfunction "D1_3") (pintype "input"))
      (node (ref "U18") (pin "8") (pinfunction "8-IN_8") (pintype "passive"))
      (node (ref "U19") (pin "9") (pinfunction "I0_9") (pintype "input"))
      (node (ref "U23") (pin "13") (pinfunction "CLR_13") (pintype "input"))
      (node (ref "U24") (pin "4") (pinfunction "EN_4") (pintype "bidirectional"))
      (node (ref "U24") (pin "9") (pinfunction "INC_9") (pintype "input"))
      (node (ref "U25") (pin "4") (pinfunction "EN_4") (pintype "bidirectional"))
      (node (ref "U9") (pin "10") (pinfunction "PRE_10") (pintype "input"))
      (node (ref "U9") (pin "12") (pinfunction "D_12") (pintype "input"))
    )
    (net (code "25") (name "ATE_CLR") (class "Default")
      (node (ref "R9") (pin "1") (pinfunction "1_1") (pintype "passive"))
      (node (ref "U17") (pin "1") (pinfunction "CLR_1") (pintype "input"))
      (node (ref "U22") (pin "1") (pinfunction "CLR_1") (pintype "input"))
      (node (ref "U22") (pin "13") (pinfunction "CLR_13") (pintype "input"))
      (node (ref "U23") (pin "1") (pinfunction "CLR_1") (pintype "input"))
      (node (ref "U9") (pin "1") (pinfunction "CLR_1") (pintype "input"))
    )
    (net (code "26") (name "BS0") (class "Default")
      (node (ref "U17") (pin "5") (pinfunction "Q2_5") (pintype "output"))
      (node (ref "U18") (pin "1") (pinfunction "1-IN_1") (pintype "passive"))
    )
    (net (code "27") (name "BS1") (class "Default")
      (node (ref "U17") (pin "15") (pinfunction "Q6_15") (pintype "output"))
      (node (ref "U18") (pin "2") (pinfunction "2-IN_2") (pintype "passive"))
    )
    (net (code "28") (name "BS2") (class "Default")
      (node (ref "U17") (pin "7") (pinfunction "Q3_7") (pintype "output"))
      (node (ref "U18") (pin "3") (pinfunction "3-IN_3") (pintype "passive"))
      (node (ref "U19") (pin "10") (pinfunction "I1_10") (pintype "input"))
    )
    (net (code "29") (name "B_SND_RD") (class "Default")
      (node (ref "C44") (pin "1") (pinfunction "1_1") (pintype "passive"))
      (node (ref "P1") (pin "15") (pinfunction "15_15") (pintype "passive"))
      (node (ref "R20") (pin "2") (pinfunction "2_2") (pintype "passive"))
    )
    (net (code "30") (name "B_VIDDAV") (class "Default")
      (node (ref "C104") (pin "2") (pinfunction "2_2") (pintype "passive"))
      (node (ref "R96") (pin "1") (pinfunction "1_1") (pintype "passive"))
      (node (ref "U25") (pin "14") (pinfunction "IND_14") (pintype "bidirectional"))
    )
    (net (code "31") (name "B_VIDRES") (class "Default")
      (node (ref "C106") (pin "1") (pinfunction "1_1") (pintype "passive"))
      (node (ref "R85") (pin "1") (pinfunction "1_1") (pintype "passive"))
      (node (ref "R93") (pin "1") (pinfunction "1_1") (pintype "passive"))
      (node (ref "U25") (pin "6") (pinfunction "INB_6") (pintype "bidirectional"))
    )
    (net (code "32") (name "D0") (class "Default")
      (node (ref "U1") (pin "37") (pinfunction "D0_37") (pintype "passive"))
      (node (ref "U14") (pin "10") (pinfunction "D0_10") (pintype "passive"))
      (node (ref "U15") (pin "11") (pinfunction "D0_11") (pintype "input"))
      (node (ref "U16") (pin "3") (pinfunction "1D_3") (pintype "input"))
      (node (ref "U17") (pin "4") (pinfunction "D2_4") (pintype "input"))
      (node (ref "U2") (pin "11") (pinfunction "I/O0_11") (pintype "bidirectional"))
      (node (ref "U3") (pin "13") (pinfunction "D0_13") (pintype "passive"))
      (node (ref "U4") (pin "31") (pinfunction "D0_31") (pintype "passive"))
      (node (ref "U5") (pin "3") (pinfunction "1D_3") (pintype "input"))
      (node (ref "U6") (pin "3") (pinfunction "OUTA_3") (pintype "bidirectional"))
    )
    (net (code "33") (name "D1") (class "Default")
      (node (ref "U1") (pin "38") (pinfunction "D1_38") (pintype "passive"))
      (node (ref "U14") (pin "12") (pinfunction "D1_12") (pintype "passive"))
      (node (ref "U15") (pin "10") (pinfunction "D1_10") (pintype "input"))
      (node (ref "U16") (pin "4") (pinfunction "2D_4") (pintype "input"))
      (node (ref "U17") (pin "14") (pinfunction "D6_14") (pintype "input"))
      (node (ref "U2") (pin "12") (pinfunction "I/O1_12") (pintype "bidirectional"))
      (node (ref "U3") (pin "14") (pinfunction "D1_14") (pintype "passive"))
      (node (ref "U4") (pin "30") (pinfunction "D1_30") (pintype "passive"))
      (node (ref "U5") (pin "4") (pinfunction "2D_4") (pintype "input"))
      (node (ref "U6") (pin "5") (pinfunction "OUTB_5") (pintype "bidirectional"))
    )
    (net (code "34") (name "D2") (class "Default")
      (node (ref "U1") (pin "39") (pinfunction "D2_39") (pintype "passive"))
      (node (ref "U14") (pin "13") (pinfunction "D2_13") (pintype "passive"))
      (node (ref "U15") (pin "9") (pinfunction "D2_9") (pintype "input"))
      (node (ref "U16") (pin "7") (pinfunction "3D_7") (pintype "input"))
      (node (ref "U17") (pin "6") (pinfunction "D3_6") (pintype "input"))
      (node (ref "U2") (pin "13") (pinfunction "I/O2_13") (pintype "bidirectional"))
      (node (ref "U3") (pin "15") (pinfunction "D2_15") (pintype "passive"))
      (node (ref "U4") (pin "29") (pinfunction "D2_29") (pintype "passive"))
      (node (ref "U5") (pin "7") (pinfunction "3D_7") (pintype "input"))
      (node (ref "U6") (pin "11") (pinfunction "OUTC_11") (pintype "bidirectional"))
    )
    (net (code "35") (name "D3") (class "Default")
      (node (ref "U1") (pin "40") (pinfunction "D3_40") (pintype "passive"))
      (node (ref "U14") (pin "14") (pinfunction "D3_14") (pintype "passive"))
      (node (ref "U15") (pin "8") (pinfunction "D3_8") (pintype "input"))
      (node (ref "U16") (pin "8") (pinfunction "4D_8") (pintype "input"))
      (node (ref "U2") (pin "15") (pinfunction "I/O3_15") (pintype "bidirectional"))
      (node (ref "U3") (pin "17") (pinfunction "D3_17") (pintype "passive"))
      (node (ref "U4") (pin "28") (pinfunction "D3_28") (pintype "passive"))
      (node (ref "U5") (pin "8") (pinfunction "4D_8") (pintype "input"))
      (node (ref "U6") (pin "13") (pinfunction "OUTD_13") (pintype "bidirectional"))
    )
    (net (code "36") (name "D4") (class "Default")
      (node (ref "U1") (pin "41") (pinfunction "D4_41") (pintype "passive"))
      (node (ref "U10") (pin "3") (pinfunction "OUTA_3") (pintype "bidirectional"))
      (node (ref "U14") (pin "15") (pinfunction "D4_15") (pintype "passive"))
      (node (ref "U15") (pin "7") (pinfunction "D4_7") (pintype "input"))
      (node (ref "U2") (pin "16") (pinfunction "I/O4_16") (pintype "bidirectional"))
      (node (ref "U3") (pin "18") (pinfunction "D4_18") (pintype "passive"))
      (node (ref "U4") (pin "27") (pinfunction "D4_27") (pintype "passive"))
      (node (ref "U5") (pin "13") (pinfunction "5D_13") (pintype "input"))
    )
    (net (code "37") (name "D5") (class "Default")
      (node (ref "U1") (pin "42") (pinfunction "D5_42") (pintype "passive"))
      (node (ref "U10") (pin "5") (pinfunction "OUTB_5") (pintype "bidirectional"))
      (node (ref "U14") (pin "16") (pinfunction "D5_16") (pintype "passive"))
      (node (ref "U15") (pin "6") (pinfunction "D5_6") (pintype "input"))
      (node (ref "U2") (pin "17") (pinfunction "I/O5_17") (pintype "bidirectional"))
      (node (ref "U3") (pin "19") (pinfunction "D5_19") (pintype "passive"))
      (node (ref "U4") (pin "26") (pinfunction "D5_26") (pintype "passive"))
      (node (ref "U5") (pin "14") (pinfunction "6D_14") (pintype "input"))
    )
    (net (code "38") (name "D6") (class "Default")
      (node (ref "U1") (pin "43") (pinfunction "D6_43") (pintype "passive"))
      (node (ref "U10") (pin "11") (pinfunction "OUTC_11") (pintype "bidirectional"))
      (node (ref "U14") (pin "17") (pinfunction "D6_17") (pintype "passive"))
      (node (ref "U15") (pin "5") (pinfunction "D6_5") (pintype "input"))
      (node (ref "U2") (pin "18") (pinfunction "I/O6_18") (pintype "bidirectional"))
      (node (ref "U3") (pin "20") (pinfunction "D6_20") (pintype "passive"))
      (node (ref "U4") (pin "25") (pinfunction "D6_25") (pintype "passive"))
      (node (ref "U5") (pin "17") (pinfunction "7D_17") (pintype "input"))
    )
    (net (code "39") (name "D7") (class "Default")
      (node (ref "U1") (pin "44") (pinfunction "D7_44") (pintype "passive"))
      (node (ref "U10") (pin "13") (pinfunction "OUTD_13") (pintype "bidirectional"))
      (node (ref "U14") (pin "18") (pinfunction "D7_18") (pintype "passive"))
      (node (ref "U15") (pin "4") (pinfunction "D7_4") (pintype "input"))
      (node (ref "U2") (pin "19") (pinfunction "I/O7_19") (pintype "bidirectional"))
      (node (ref "U3") (pin "21") (pinfunction "D7_21") (pintype "passive"))
      (node (ref "U4") (pin "24") (pinfunction "D7_24") (pintype "passive"))
      (node (ref "U5") (pin "18") (pinfunction "8D_18") (pintype "input"))
    )
    (net (code "40") (name "DAC") (class "Default")
      (node (ref "U15") (pin "12") (pinfunction "~{CS}_12") (pintype "input"))
      (node (ref "U8") (pin "13") (pinfunction "Y2_13") (pintype "output"))
    )
    (net (code "41") (name "DAC-OUT") (class "Default")
      (node (ref "R61") (pin "2") (pinfunction "2_2") (pintype "passive"))
      (node (ref "R62") (pin "2") (pinfunction "2_2") (pintype "passive"))
      (node (ref "U29") (pin "8") (pinfunction "OUT_8") (pintype "output"))
      (node (ref "U29") (pin "9") (pinfunction "-IN_9") (pintype "input"))
    )
    (net (code "42") (name "FFO") (class "Default")
      (node (ref "U24") (pin "1") (pinfunction "INA_1") (pintype "input"))
      (node (ref "U9") (pin "9") (pinfunction "Q_9") (pintype "output"))
    )
    (net (code "43") (name "FIRQ") (class "Default")
      (node (ref "R7") (pin "1") (pinfunction "1_1") (pintype "passive"))
      (node (ref "U14") (pin "2") (pinfunction "~{IRQ}_2") (pintype "passive"))
      (node (ref "U4") (pin "4") (pinfunction "~{FIRQ}_4") (pintype "passive"))
    )
    (net (code "44") (name "GND") (class "Default")
      (node (ref "C10") (pin "2") (pinfunction "2_2") (pintype "passive"))
      (node (ref "C100") (pin "-") (pinfunction "-_-") (pintype "passive"))
      (node (ref "C103") (pin "-") (pinfunction "-_-") (pintype "passive"))
      (node (ref "C104") (pin "1") (pinfunction "1_1") (pintype "passive"))
      (node (ref "C105") (pin "1") (pinfunction "1_1") (pintype "passive"))
      (node (ref "C106") (pin "2") (pinfunction "2_2") (pintype "passive"))
      (node (ref "C107") (pin "2") (pinfunction "2_2") (pintype "passive"))
      (node (ref "C11") (pin "2") (pinfunction "2_2") (pintype "passive"))
      (node (ref "C12") (pin "2") (pinfunction "2_2") (pintype "passive"))
      (node (ref "C13") (pin "2") (pinfunction "2_2") (pintype "passive"))
      (node (ref "C14") (pin "2") (pinfunction "2_2") (pintype "passive"))
      (node (ref "C15") (pin "2") (pinfunction "2_2") (pintype "passive"))
      (node (ref "C16") (pin "2") (pinfunction "2_2") (pintype "passive"))
      (node (ref "C17") (pin "2") (pinfunction "2_2") (pintype "passive"))
      (node (ref "C18") (pin "2") (pinfunction "2_2") (pintype "passive"))
      (node (ref "C19") (pin "2") (pinfunction "2_2") (pintype "passive"))
      (node (ref "C2") (pin "2") (pinfunction "2_2") (pintype "passive"))
      (node (ref "C20") (pin "2") (pinfunction "2_2") (pintype "passive"))
      (node (ref "C21") (pin "2") (pinfunction "2_2") (pintype "passive"))
      (node (ref "C22") (pin "2") (pinfunction "2_2") (pintype "passive"))
      (node (ref "C23") (pin "2") (pinfunction "2_2") (pintype "passive"))
      (node (ref "C24") (pin "2") (pinfunction "2_2") (pintype "passive"))
      (node (ref "C25") (pin "2") (pinfunction "2_2") (pintype "passive"))
      (node (ref "C26") (pin "2") (pinfunction "2_2") (pintype "passive"))
      (node (ref "C28") (pin "2") (pinfunction "2_2") (pintype "passive"))
      (node (ref "C3") (pin "2") (pinfunction "2_2") (pintype "passive"))
      (node (ref "C35") (pin "2") (pinfunction "2_2") (pintype "passive"))
      (node (ref "C36") (pin "2") (pinfunction "2_2") (pintype "passive"))
      (node (ref "C37") (pin "2") (pinfunction "2_2") (pintype "passive"))
      (node (ref "C38") (pin "2") (pinfunction "2_2") (pintype "passive"))
      (node (ref "C39") (pin "2") (pinfunction "2_2") (pintype "passive"))
      (node (ref "C4") (pin "2") (pinfunction "2_2") (pintype "passive"))
      (node (ref "C40") (pin "2") (pinfunction "2_2") (pintype "passive"))
      (node (ref "C41") (pin "2") (pinfunction "2_2") (pintype "passive"))
      (node (ref "C42") (pin "2") (pinfunction "2_2") (pintype "passive"))
      (node (ref "C43") (pin "2") (pinfunction "2_2") (pintype "passive"))
      (node (ref "C44") (pin "2") (pinfunction "2_2") (pintype "passive"))
      (node (ref "C45") (pin "2") (pinfunction "2_2") (pintype "passive"))
      (node (ref "C49") (pin "2") (pinfunction "2_2") (pintype "passive"))
      (node (ref "C5") (pin "2") (pinfunction "2_2") (pintype "passive"))
      (node (ref "C6") (pin "2") (pinfunction "2_2") (pintype "passive"))
      (node (ref "C7") (pin "2") (pinfunction "2_2") (pintype "passive"))
      (node (ref "C70") (pin "-") (pinfunction "-_-") (pintype "passive"))
      (node (ref "C72") (pin "2") (pinfunction "2_2") (pintype "passive"))
      (node (ref "C74") (pin "2") (pinfunction "2_2") (pintype "passive"))
      (node (ref "C8") (pin "2") (pinfunction "2_2") (pintype "passive"))
      (node (ref "C9") (pin "2") (pinfunction "2_2") (pintype "passive"))
      (node (ref "C99") (pin "2") (pinfunction "2_2") (pintype "passive"))
      (node (ref "MTG1") (pin "P1") (pinfunction "P$1_P1") (pintype "bidirectional"))
      (node (ref "MTG2") (pin "P1") (pinfunction "P$1_P1") (pintype "bidirectional"))
      (node (ref "MTG3") (pin "P1") (pinfunction "P$1_P1") (pintype "bidirectional"))
      (node (ref "MTG4") (pin "P1") (pinfunction "P$1_P1") (pintype "bidirectional"))
      (node (ref "P1") (pin "1") (pinfunction "1_1") (pintype "passive"))
      (node (ref "P6") (pin "2") (pinfunction "2_2") (pintype "passive"))
      (node (ref "Q1") (pin "2") (pinfunction "E_2") (pintype "passive"))
      (node (ref "R4") (pin "2") (pinfunction "2_2") (pintype "passive"))
      (node (ref "R83") (pin "1") (pinfunction "1_1") (pintype "passive"))
      (node (ref "U1") (pin "1") (pinfunction "VSS_1") (pintype "passive"))
      (node (ref "U10") (pin "4") (pinfunction "EN_4") (pintype "bidirectional"))
      (node (ref "U10") (pin "8") (pinfunction "GND_8") (pintype "power_in"))
      (node (ref "U11") (pin "4") (pinfunction "EN_4") (pintype "bidirectional"))
      (node (ref "U11") (pin "8") (pinfunction "GND_8") (pintype "power_in"))
      (node (ref "U12") (pin "16") (pinfunction "VSS_16") (pintype "passive"))
      (node (ref "U12") (pin "22") (pinfunction "~{CS}_22") (pintype "passive"))
      (node (ref "U13") (pin "16") (pinfunction "VSS_16") (pintype "passive"))
      (node (ref "U13") (pin "22") (pinfunction "~{CS}_22") (pintype "passive"))
      (node (ref "U14") (pin "1") (pinfunction "VSS-1_1") (pintype "passive"))
      (node (ref "U14") (pin "11") (pinfunction "VSS-11_11") (pintype "passive"))
      (node (ref "U15") (pin "3") (pinfunction "GND_3") (pintype "power_in"))
      (node (ref "U16") (pin "10") (pinfunction "GND_10") (pintype "power_in"))
      (node (ref "U17") (pin "8") (pinfunction "GND_8") (pintype "power_in"))
      (node (ref "U18") (pin "10") (pinfunction "VSS_10") (pintype "passive"))
      (node (ref "U19") (pin "7") (pinfunction "GND_7") (pintype "power_in"))
      (node (ref "U2") (pin "14") (pinfunction "VSS_14") (pintype "power_in"))
      (node (ref "U20") (pin "13") (pinfunction "B_13") (pintype "input"))
      (node (ref "U20") (pin "8") (pinfunction "GND_8") (pintype "power_in"))
      (node (ref "U21") (pin "7") (pinfunction "GND_7") (pintype "power_in"))
      (node (ref "U22") (pin "7") (pinfunction "GND_7") (pintype "power_in"))
      (node (ref "U23") (pin "7") (pinfunction "GND_7") (pintype "power_in"))
      (node (ref "U24") (pin "8") (pinfunction "GND_8") (pintype "power_in"))
      (node (ref "U25") (pin "8") (pinfunction "GND_8") (pintype "power_in"))
      (node (ref "U26") (pin "7") (pinfunction "GND_7") (pintype "power_in"))
      (node (ref "U28") (pin "3") (pinfunction "VSS_3") (pintype "passive"))
      (node (ref "U3") (pin "16") (pinfunction "VSS_16") (pintype "passive"))
      (node (ref "U3") (pin "22") (pinfunction "~{CS}_22") (pintype "passive"))
      (node (ref "U4") (pin "1") (pinfunction "VSS_1") (pintype "passive"))
      (node (ref "U4") (pin "39") (pinfunction "TSC_39") (pintype "passive"))
      (node (ref "U5") (pin "10") (pinfunction "GND_10") (pintype "power_in"))
      (node (ref "U6") (pin "4") (pinfunction "EN_4") (pintype "bidirectional"))
      (node (ref "U6") (pin "8") (pinfunction "GND_8") (pintype "power_in"))
      (node (ref "U7") (pin "4") (pinfunction "EN_4") (pintype "bidirectional"))
      (node (ref "U7") (pin "8") (pinfunction "GND_8") (pintype "power_in"))
      (node (ref "U8") (pin "8") (pinfunction "GND_8") (pintype "power_in"))
      (node (ref "U9") (pin "7") (pinfunction "GND_7") (pintype "power_in"))
      (node (ref "W8") (pin "1") (pinfunction "1_1") (pintype "passive"))
      (node (ref "Y2") (pin "2") (pinfunction "GND_2") (pintype "bidirectional"))
    )
    (net (code "45") (name "IRQ") (class "Default")
      (node (ref "R5") (pin "1") (pinfunction "1_1") (pintype "passive"))
      (node (ref "U23") (pin "9") (pinfunction "Q_9") (pintype "output"))
      (node (ref "U24") (pin "15") (pinfunction "IND_15") (pintype "input"))
      (node (ref "U4") (pin "3") (pinfunction "~{IRQ}_3") (pintype "passive"))
    )
    (net (code "46") (name "Net-(C47-Pad1)") (class "Default")
      (node (ref "C47") (pin "1") (pinfunction "1_1") (pintype "passive"))
      (node (ref "Y1") (pin "2") (pinfunction "2_2") (pintype "passive"))
    )
    (net (code "47") (name "Net-(C52-Pad2)") (class "Default")
      (node (ref "C52") (pin "2") (pinfunction "2_2") (pintype "passive"))
      (node (ref "R38") (pin "2") (pinfunction "2_2") (pintype "passive"))
      (node (ref "R39") (pin "1") (pinfunction "1_1") (pintype "passive"))
    )
    (net (code "48") (name "Net-(C54-Pad1)") (class "Default")
      (node (ref "C54") (pin "1") (pinfunction "1_1") (pintype "passive"))
      (node (ref "R44") (pin "1") (pinfunction "1_1") (pintype "passive"))
      (node (ref "R45") (pin "2") (pinfunction "2_2") (pintype "passive"))
      (node (ref "R46") (pin "2") (pinfunction "2_2") (pintype "passive"))
    )
    (net (code "49") (name "Net-(C58-Pad2)") (class "Default")
      (node (ref "C58") (pin "2") (pinfunction "2_2") (pintype "passive"))
      (node (ref "R35") (pin "1") (pinfunction "1_1") (pintype "passive"))
      (node (ref "R36") (pin "2") (pinfunction "2_2") (pintype "passive"))
    )
    (net (code "50") (name "Net-(C61-Pad1)") (class "Default")
      (node (ref "C61") (pin "1") (pinfunction "1_1") (pintype "passive"))
      (node (ref "R40") (pin "1") (pinfunction "1_1") (pintype "passive"))
      (node (ref "R51") (pin "2") (pinfunction "2_2") (pintype "passive"))
      (node (ref "R52") (pin "2") (pinfunction "2_2") (pintype "passive"))
    )
    (net (code "51") (name "Net-(C69-Pad1)") (class "Default")
      (node (ref "C69") (pin "1") (pinfunction "1_1") (pintype "passive"))
      (node (ref "R62") (pin "1") (pinfunction "1_1") (pintype "passive"))
      (node (ref "R63") (pin "2") (pinfunction "2_2") (pintype "passive"))
      (node (ref "R64") (pin "2") (pinfunction "2_2") (pintype "passive"))
    )
    (net (code "52") (name "Net-(C74-Pad1)") (class "Default")
      (node (ref "C74") (pin "1") (pinfunction "1_1") (pintype "passive"))
      (node (ref "L1") (pin "2") (pinfunction "2_2") (pintype "passive"))
      (node (ref "P6") (pin "1") (pinfunction "1_1") (pintype "passive"))
    )
    (net (code "53") (name "Net-(C81-Pad+)") (class "Default")
      (node (ref "C81") (pin "+") (pinfunction "+_+") (pintype "passive"))
      (node (ref "R70") (pin "1") (pinfunction "1_1") (pintype "passive"))
      (node (ref "R71") (pin "2") (pinfunction "2_2") (pintype "passive"))
    )
    (net (code "54") (name "Net-(C88-Pad1)") (class "Default")
      (node (ref "C88") (pin "1") (pinfunction "1_1") (pintype "passive"))
      (node (ref "L2") (pin "1") (pinfunction "1_1") (pintype "passive"))
      (node (ref "P6") (pin "5") (pinfunction "5_5") (pintype "passive"))
      (node (ref "P6") (pin "6") (pinfunction "6_6") (pintype "passive"))
    )
    (net (code "55") (name "Net-(CR1-PadC)") (class "Default")
      (node (ref "CR1") (pin "C") (pinfunction "C_C") (pintype "passive"))
      (node (ref "R30") (pin "1") (pinfunction "1_1") (pintype "passive"))
    )
    (net (code "56") (name "Net-(CR2-C)") (class "Default")
      (node (ref "C73") (pin "+") (pinfunction "+_+") (pintype "passive"))
      (node (ref "CR2") (pin "3") (pinfunction "C_3") (pintype "passive"))
      (node (ref "R54") (pin "2") (pinfunction "2_2") (pintype "passive"))
      (node (ref "U32") (pin "10") (pinfunction "+IN_10") (pintype "input"))
      (node (ref "U33") (pin "12") (pinfunction "+IN_12") (pintype "input"))
      (node (ref "U33") (pin "3") (pinfunction "+IN_3") (pintype "input"))
      (node (ref "U33") (pin "5") (pinfunction "+IN_5") (pintype "input"))
    )
    (net (code "57") (name "Net-(P1-Pad13)") (class "Default")
      (node (ref "P1") (pin "13") (pinfunction "13_13") (pintype "passive"))
      (node (ref "R96") (pin "2") (pinfunction "2_2") (pintype "passive"))
    )
    (net (code "58") (name "Net-(P1-Pad16)") (class "Default")
      (node (ref "P1") (pin "16") (pinfunction "16_16") (pintype "passive"))
      (node (ref "R95") (pin "2") (pinfunction "2_2") (pintype "passive"))
    )
    (net (code "59") (name "Net-(P1-Pad17)") (class "Default")
      (node (ref "P1") (pin "17") (pinfunction "17_17") (pintype "passive"))
      (node (ref "R93") (pin "2") (pinfunction "2_2") (pintype "passive"))
    )
    (net (code "60") (name "Net-(P1-Pad18)") (class "Default")
      (node (ref "P1") (pin "18") (pinfunction "18_18") (pintype "passive"))
      (node (ref "R94") (pin "2") (pinfunction "2_2") (pintype "passive"))
    )
    (net (code "61") (name "Net-(Q1-B)") (class "Default")
      (node (ref "C62") (pin "2") (pinfunction "2_2") (pintype "passive"))
      (node (ref "Q1") (pin "1") (pinfunction "B_1") (pintype "passive"))
      (node (ref "R28") (pin "2") (pinfunction "2_2") (pintype "passive"))
    )
    (net (code "62") (name "Net-(Q1-C)") (class "Default")
      (node (ref "Q1") (pin "3") (pinfunction "C_3") (pintype "passive"))
      (node (ref "R27") (pin "1") (pinfunction "1_1") (pintype "passive"))
      (node (ref "U4") (pin "34") (pinfunction "E_34") (pintype "passive"))
    )
    (net (code "63") (name "Net-(RV1-E)") (class "Default")
      (node (ref "R87") (pin "2") (pinfunction "2_2") (pintype "passive"))
      (node (ref "RV1") (pin "3") (pinfunction "E_3") (pintype "passive"))
    )
    (net (code "64") (name "Net-(U1-DAO)") (class "Default")
      (node (ref "C46") (pin "-") (pinfunction "-_-") (pintype "passive"))
      (node (ref "U1") (pin "36") (pinfunction "DAO_36") (pintype "passive"))
    )
    (net (code "65") (name "Net-(U1-VCC)") (class "Default")
      (node (ref "C103") (pin "+") (pinfunction "+_+") (pintype "passive"))
      (node (ref "C99") (pin "1") (pinfunction "1_1") (pintype "passive"))
      (node (ref "R89") (pin "1") (pinfunction "1_1") (pintype "passive"))
      (node (ref "U1") (pin "17") (pinfunction "VCC_17") (pintype "passive"))
    )
    (net (code "66") (name "Net-(U2-CS2)") (class "Default")
      (node (ref "R1") (pin "1") (pinfunction "1_1") (pintype "passive"))
      (node (ref "U2") (pin "26") (pinfunction "CS2_26") (pintype "input"))
    )
    (net (code "67") (name "Net-(U2-~{CS1})") (class "Default")
      (node (ref "U2") (pin "20") (pinfunction "~{CS1}_20") (pintype "input"))
      (node (ref "U20") (pin "12") (pinfunction "Y0_12") (pintype "output"))
    )
    (net (code "68") (name "Net-(U4-~{HALT})") (class "Default")
      (node (ref "R6") (pin "1") (pinfunction "1_1") (pintype "passive"))
      (node (ref "U4") (pin "40") (pinfunction "~{HALT}_40") (pintype "passive"))
    )
    (net (code "69") (name "Net-(U4-~{NMI})") (class "Default")
      (node (ref "R2") (pin "1") (pinfunction "1_1") (pintype "passive"))
      (node (ref "U4") (pin "2") (pinfunction "~{NMI}_2") (pintype "passive"))
    )
    (net (code "70") (name "Net-(U5A-1Q)") (class "Default")
      (node (ref "U5") (pin "2") (pinfunction "1Q_2") (pintype "tri_state"))
      (node (ref "U7") (pin "1") (pinfunction "INA_1") (pintype "input"))
    )
    (net (code "71") (name "Net-(U5A-2Q)") (class "Default")
      (node (ref "U5") (pin "5") (pinfunction "2Q_5") (pintype "tri_state"))
      (node (ref "U7") (pin "7") (pinfunction "INB_7") (pintype "input"))
    )
    (net (code "72") (name "Net-(U5A-3Q)") (class "Default")
      (node (ref "U5") (pin "6") (pinfunction "3Q_6") (pintype "tri_state"))
      (node (ref "U7") (pin "9") (pinfunction "INC_9") (pintype "input"))
    )
    (net (code "73") (name "Net-(U5A-4Q)") (class "Default")
      (node (ref "U5") (pin "9") (pinfunction "4Q_9") (pintype "tri_state"))
      (node (ref "U7") (pin "15") (pinfunction "IND_15") (pintype "input"))
    )
    (net (code "74") (name "Net-(U6-INA)") (class "Default")
      (node (ref "R11") (pin "1") (pinfunction "1_1") (pintype "passive"))
      (node (ref "U6") (pin "2") (pinfunction "INA_2") (pintype "bidirectional"))
      (node (ref "U7") (pin "2") (pinfunction "OUTA_2") (pintype "bidirectional"))
    )
    (net (code "75") (name "Net-(U6-INB)") (class "Default")
      (node (ref "R13") (pin "1") (pinfunction "1_1") (pintype "passive"))
      (node (ref "U6") (pin "6") (pinfunction "INB_6") (pintype "bidirectional"))
      (node (ref "U7") (pin "6") (pinfunction "OUTB_6") (pintype "bidirectional"))
    )
    (net (code "76") (name "Net-(U6-INC)") (class "Default")
      (node (ref "R14") (pin "1") (pinfunction "1_1") (pintype "passive"))
      (node (ref "U6") (pin "10") (pinfunction "INC_10") (pintype "bidirectional"))
      (node (ref "U7") (pin "10") (pinfunction "OUTC_10") (pintype "bidirectional"))
    )
    (net (code "77") (name "Net-(U6-IND)") (class "Default")
      (node (ref "R12") (pin "1") (pinfunction "1_1") (pintype "passive"))
      (node (ref "U6") (pin "14") (pinfunction "IND_14") (pintype "bidirectional"))
      (node (ref "U7") (pin "14") (pinfunction "OUTD_14") (pintype "bidirectional"))
    )
    (net (code "78") (name "Net-(U9A-D)") (class "Default")
      (node (ref "U9") (pin "2") (pinfunction "D_2") (pintype "input"))
      (node (ref "U9") (pin "6") (pinfunction "~{Q}_6") (pintype "output"))
    )
    (net (code "79") (name "Net-(U10-INA)") (class "Default")
      (node (ref "R15") (pin "1") (pinfunction "1_1") (pintype "passive"))
      (node (ref "U10") (pin "2") (pinfunction "INA_2") (pintype "bidirectional"))
      (node (ref "U11") (pin "2") (pinfunction "OUTA_2") (pintype "bidirectional"))
    )
    (net (code "80") (name "Net-(U10-INB)") (class "Default")
      (node (ref "R16") (pin "1") (pinfunction "1_1") (pintype "passive"))
      (node (ref "U10") (pin "6") (pinfunction "INB_6") (pintype "bidirectional"))
      (node (ref "U11") (pin "6") (pinfunction "OUTB_6") (pintype "bidirectional"))
    )
    (net (code "81") (name "Net-(U10-INC)") (class "Default")
      (node (ref "R17") (pin "1") (pinfunction "1_1") (pintype "passive"))
      (node (ref "U10") (pin "10") (pinfunction "INC_10") (pintype "bidirectional"))
      (node (ref "U11") (pin "10") (pinfunction "OUTC_10") (pintype "bidirectional"))
    )
    (net (code "82") (name "Net-(U10-IND)") (class "Default")
      (node (ref "R18") (pin "1") (pinfunction "1_1") (pintype "passive"))
      (node (ref "U10") (pin "14") (pinfunction "IND_14") (pintype "bidirectional"))
      (node (ref "U11") (pin "14") (pinfunction "OUTD_14") (pintype "bidirectional"))
    )
    (net (code "83") (name "Net-(U10-~{INA})") (class "Default")
      (node (ref "R82") (pin "1") (pinfunction "1_1") (pintype "passive"))
      (node (ref "R83") (pin "2") (pinfunction "2_2") (pintype "passive"))
      (node (ref "U10") (pin "1") (pinfunction "~{INA}_1") (pintype "bidirectional"))
      (node (ref "U10") (pin "15") (pinfunction "~{IND}_15") (pintype "bidirectional"))
      (node (ref "U10") (pin "7") (pinfunction "~{INB}_7") (pintype "bidirectional"))
      (node (ref "U10") (pin "9") (pinfunction "~{INC}_9") (pintype "bidirectional"))
      (node (ref "U25") (pin "1") (pinfunction "~{INA}_1") (pintype "bidirectional"))
      (node (ref "U25") (pin "15") (pinfunction "~{IND}_15") (pintype "bidirectional"))
      (node (ref "U25") (pin "7") (pinfunction "~{INB}_7") (pintype "bidirectional"))
      (node (ref "U25") (pin "9") (pinfunction "~{INC}_9") (pintype "bidirectional"))
      (node (ref "U6") (pin "1") (pinfunction "~{INA}_1") (pintype "bidirectional"))
      (node (ref "U6") (pin "15") (pinfunction "~{IND}_15") (pintype "bidirectional"))
      (node (ref "U6") (pin "7") (pinfunction "~{INB}_7") (pintype "bidirectional"))
      (node (ref "U6") (pin "9") (pinfunction "~{INC}_9") (pintype "bidirectional"))
    )
    (net (code "84") (name "Net-(U11-INA)") (class "Default")
      (node (ref "U11") (pin "1") (pinfunction "INA_1") (pintype "input"))
      (node (ref "U5") (pin "12") (pinfunction "5Q_12") (pintype "tri_state"))
    )
    (net (code "85") (name "Net-(U11-INB)") (class "Default")
      (node (ref "U11") (pin "7") (pinfunction "INB_7") (pintype "input"))
      (node (ref "U5") (pin "15") (pinfunction "6Q_15") (pintype "tri_state"))
    )
    (net (code "86") (name "Net-(U11-INC)") (class "Default")
      (node (ref "U11") (pin "9") (pinfunction "INC_9") (pintype "input"))
      (node (ref "U5") (pin "16") (pinfunction "7Q_16") (pintype "tri_state"))
    )
    (net (code "87") (name "Net-(U11-IND)") (class "Default")
      (node (ref "U11") (pin "15") (pinfunction "IND_15") (pintype "input"))
      (node (ref "U5") (pin "19") (pinfunction "8Q_19") (pintype "tri_state"))
    )
    (net (code "88") (name "Net-(U12-~{OE})") (class "Default")
      (node (ref "U12") (pin "24") (pinfunction "~{OE}_24") (pintype "passive"))
      (node (ref "U19") (pin "8") (pinfunction "O_8") (pintype "output"))
      (node (ref "U26") (pin "11") (pinfunction "I_11") (pintype "input"))
    )
    (net (code "89") (name "Net-(U13-~{OE})") (class "Default")
      (node (ref "U13") (pin "24") (pinfunction "~{OE}_24") (pintype "passive"))
      (node (ref "U26") (pin "10") (pinfunction "O_10") (pintype "output"))
    )
    (net (code "90") (name "Net-(U14-CLK)") (class "Default")
      (node (ref "U14") (pin "23") (pinfunction "CLK_23") (pintype "passive"))
      (node (ref "U28") (pin "2") (pinfunction "CLK_2") (pintype "passive"))
    )
    (net (code "91") (name "Net-(U14-OSC)") (class "Default")
      (node (ref "U14") (pin "24") (pinfunction "OSC_24") (pintype "passive"))
      (node (ref "U26") (pin "6") (pinfunction "O_6") (pintype "output"))
    )
    (net (code "92") (name "Net-(U14-SH1)") (class "Default")
      (node (ref "U14") (pin "20") (pinfunction "SH1_20") (pintype "passive"))
      (node (ref "U28") (pin "6") (pinfunction "SAM1_6") (pintype "passive"))
    )
    (net (code "93") (name "Net-(U14-SH2)") (class "Default")
      (node (ref "U14") (pin "19") (pinfunction "SH2_19") (pintype "passive"))
      (node (ref "U28") (pin "5") (pinfunction "SAM2_5") (pintype "passive"))
    )
    (net (code "94") (name "Net-(U14-SO)") (class "Default")
      (node (ref "U14") (pin "21") (pinfunction "SO_21") (pintype "passive"))
      (node (ref "U28") (pin "4") (pinfunction "SO_4") (pintype "passive"))
    )
    (net (code "95") (name "Net-(U15-OUT1)") (class "Default")
      (node (ref "C63") (pin "+") (pinfunction "+_+") (pintype "passive"))
      (node (ref "R68") (pin "2") (pinfunction "2_2") (pintype "passive"))
      (node (ref "R69") (pin "1") (pinfunction "1_1") (pintype "passive"))
      (node (ref "U15") (pin "1") (pinfunction "OUT1_1") (pintype "passive"))
    )
    (net (code "96") (name "Net-(U15-VREF)") (class "Default")
      (node (ref "C98") (pin "1") (pinfunction "1_1") (pintype "passive"))
      (node (ref "U15") (pin "15") (pinfunction "VREF_15") (pintype "input"))
      (node (ref "U29") (pin "12") (pinfunction "+IN_12") (pintype "input"))
    )
    (net (code "97") (name "Net-(U16A-1Q)") (class "Default")
      (node (ref "R24") (pin "1") (pinfunction "1_1") (pintype "passive"))
      (node (ref "U16") (pin "2") (pinfunction "1Q_2") (pintype "tri_state"))
      (node (ref "U3") (pin "3") (pinfunction "A15_3") (pintype "passive"))
    )
    (net (code "98") (name "Net-(U16A-2Q)") (class "Default")
      (node (ref "R23") (pin "1") (pinfunction "1_1") (pintype "passive"))
      (node (ref "U16") (pin "5") (pinfunction "2Q_5") (pintype "tri_state"))
      (node (ref "U3") (pin "2") (pinfunction "A16_2") (pintype "passive"))
    )
    (net (code "99") (name "Net-(U16A-3Q)") (class "Default")
      (node (ref "R22") (pin "1") (pinfunction "1_1") (pintype "passive"))
      (node (ref "U16") (pin "6") (pinfunction "3Q_6") (pintype "tri_state"))
      (node (ref "U3") (pin "30") (pinfunction "A17_30") (pintype "passive"))
    )
    (net (code "100") (name "Net-(U16A-4Q)") (class "Default")
      (node (ref "R26") (pin "1") (pinfunction "1_1") (pintype "passive"))
      (node (ref "U16") (pin "9") (pinfunction "4Q_9") (pintype "tri_state"))
      (node (ref "U3") (pin "31") (pinfunction "A18_31") (pintype "passive"))
    )
    (net (code "101") (name "Net-(U16A-CLK)") (class "Default")
      (node (ref "U16") (pin "11") (pinfunction "CLK_11") (pintype "input"))
      (node (ref "U26") (pin "8") (pinfunction "O_8") (pintype "output"))
    )
    (net (code "102") (name "Net-(U16A-OC)") (class "Default")
      (node (ref "U16") (pin "1") (pinfunction "OC_1") (pintype "input"))
      (node (ref "U8") (pin "15") (pinfunction "Y0_15") (pintype "output"))
    )
    (net (code "103") (name "Net-(U18-7-IN)") (class "Default")
      (node (ref "R91") (pin "1") (pinfunction "1_1") (pintype "passive"))
      (node (ref "U18") (pin "7") (pinfunction "7-IN_7") (pintype "passive"))
    )
    (net (code "104") (name "Net-(U18-11-IN)") (class "Default")
      (node (ref "U18") (pin "11") (pinfunction "11-IN_11") (pintype "passive"))
      (node (ref "U19") (pin "6") (pinfunction "O_6") (pintype "output"))
      (node (ref "U3") (pin "24") (pinfunction "~{OE}_24") (pintype "passive"))
    )
    (net (code "105") (name "Net-(U19A-I0)") (class "Default")
      (node (ref "U19") (pin "1") (pinfunction "I0_1") (pintype "input"))
      (node (ref "U21") (pin "2") (pinfunction "O_2") (pintype "output"))
    )
    (net (code "106") (name "Net-(U19B-I0)") (class "Default")
      (node (ref "U19") (pin "3") (pinfunction "I0_3") (pintype "input"))
      (node (ref "U20") (pin "5") (pinfunction "Y1_5") (pintype "output"))
    )
    (net (code "107") (name "Net-(U19B-I1)") (class "Default")
      (node (ref "U19") (pin "4") (pinfunction "I1_4") (pintype "input"))
      (node (ref "U20") (pin "6") (pinfunction "Y2_6") (pintype "output"))
    )
    (net (code "108") (name "Net-(U19B-I2)") (class "Default")
      (node (ref "U19") (pin "5") (pinfunction "I2_5") (pintype "input"))
      (node (ref "U20") (pin "7") (pinfunction "Y3_7") (pintype "output"))
      (node (ref "U26") (pin "9") (pinfunction "I_9") (pintype "input"))
    )
    (net (code "109") (name "Net-(U19C-I2)") (class "Default")
      (node (ref "U19") (pin "11") (pinfunction "I2_11") (pintype "input"))
      (node (ref "U26") (pin "12") (pinfunction "O_12") (pintype "output"))
    )
    (net (code "110") (name "Net-(U20A-Y0)") (class "Default")
      (node (ref "U20") (pin "15") (pinfunction "G_15") (pintype "input"))
      (node (ref "U20") (pin "4") (pinfunction "Y0_4") (pintype "output"))
    )
    (net (code "111") (name "Net-(U20B-Y1)") (class "Default")
      (node (ref "U20") (pin "11") (pinfunction "Y1_11") (pintype "output"))
      (node (ref "U8") (pin "4") (pinfunction "G2A_4") (pintype "input"))
      (node (ref "U8") (pin "5") (pinfunction "G2B_5") (pintype "input"))
    )
    (net (code "112") (name "Net-(U21C-I)") (class "Default")
      (node (ref "C100") (pin "+") (pinfunction "+_+") (pintype "passive"))
      (node (ref "CR1") (pin "A") (pinfunction "A_A") (pintype "passive"))
      (node (ref "R29") (pin "1") (pinfunction "1_1") (pintype "passive"))
      (node (ref "U21") (pin "9") (pinfunction "I_9") (pintype "input"))
    )
    (net (code "113") (name "Net-(U21C-O)") (class "Default")
      (node (ref "U21") (pin "1") (pinfunction "I_1") (pintype "input"))
      (node (ref "U21") (pin "8") (pinfunction "O_8") (pintype "output"))
    )
    (net (code "114") (name "Net-(U21F-I)") (class "Default")
      (node (ref "U21") (pin "5") (pinfunction "I_5") (pintype "input"))
      (node (ref "Y2") (pin "3") (pinfunction "OUT_3") (pintype "bidirectional"))
    )
    (net (code "115") (name "Net-(U21F-O)") (class "Default")
      (node (ref "U21") (pin "6") (pinfunction "O_6") (pintype "output"))
      (node (ref "U22") (pin "3") (pinfunction "CLK_3") (pintype "input"))
      (node (ref "U23") (pin "3") (pinfunction "CLK_3") (pintype "input"))
    )
    (net (code "116") (name "Net-(U22A-D)") (class "Default")
      (node (ref "U22") (pin "2") (pinfunction "D_2") (pintype "input"))
      (node (ref "U23") (pin "5") (pinfunction "Q_5") (pintype "output"))
      (node (ref "U4") (pin "35") (pinfunction "Q_35") (pintype "passive"))
    )
    (net (code "117") (name "Net-(U22A-PRE)") (class "Default")
      (node (ref "R10") (pin "1") (pinfunction "1_1") (pintype "passive"))
      (node (ref "U22") (pin "10") (pinfunction "PRE_10") (pintype "input"))
      (node (ref "U22") (pin "11") (pinfunction "CLK_11") (pintype "input"))
      (node (ref "U22") (pin "12") (pinfunction "D_12") (pintype "input"))
      (node (ref "U22") (pin "4") (pinfunction "PRE_4") (pintype "input"))
      (node (ref "U23") (pin "4") (pinfunction "PRE_4") (pintype "input"))
      (node (ref "U9") (pin "4") (pinfunction "PRE_4") (pintype "input"))
    )
    (net (code "118") (name "Net-(U22A-Q)") (class "Default")
      (node (ref "U22") (pin "5") (pinfunction "Q_5") (pintype "output"))
      (node (ref "U9") (pin "3") (pinfunction "CLK_3") (pintype "input"))
    )
    (net (code "119") (name "Net-(U23B-CLK)") (class "Default")
      (node (ref "U23") (pin "11") (pinfunction "CLK_11") (pintype "input"))
      (node (ref "U25") (pin "13") (pinfunction "OUTD_13") (pintype "bidirectional"))
    )
    (net (code "120") (name "Net-(U23B-D)") (class "Default")
      (node (ref "R4") (pin "1") (pinfunction "1_1") (pintype "passive"))
      (node (ref "U23") (pin "12") (pinfunction "D_12") (pintype "input"))
      (node (ref "U24") (pin "12") (pinfunction "~{EN}_12") (pintype "bidirectional"))
      (node (ref "U25") (pin "12") (pinfunction "~{EN}_12") (pintype "bidirectional"))
      (node (ref "U5") (pin "1") (pinfunction "OC_1") (pintype "input"))
    )
    (net (code "121") (name "Net-(U24-OUTA)") (class "Default")
      (node (ref "R21") (pin "1") (pinfunction "1_1") (pintype "passive"))
      (node (ref "U24") (pin "2") (pinfunction "OUTA_2") (pintype "bidirectional"))
    )
    (net (code "122") (name "Net-(U24-OUTB)") (class "Default")
      (node (ref "R20") (pin "1") (pinfunction "1_1") (pintype "passive"))
      (node (ref "U24") (pin "6") (pinfunction "OUTB_6") (pintype "bidirectional"))
    )
    (net (code "123") (name "Net-(U24-OUTD)") (class "Default")
      (node (ref "R19") (pin "1") (pinfunction "1_1") (pintype "passive"))
      (node (ref "U24") (pin "14") (pinfunction "OUTD_14") (pintype "bidirectional"))
    )
    (net (code "124") (name "Net-(U26A-I)") (class "Default")
      (node (ref "C49") (pin "1") (pinfunction "1_1") (pintype "passive"))
      (node (ref "R32") (pin "1") (pinfunction "1_1") (pintype "passive"))
      (node (ref "U26") (pin "1") (pinfunction "I_1") (pintype "input"))
      (node (ref "Y1") (pin "1") (pinfunction "1_1") (pintype "passive"))
    )
    (net (code "125") (name "Net-(U26A-O)") (class "Default")
      (node (ref "R32") (pin "2") (pinfunction "2_2") (pintype "passive"))
      (node (ref "R34") (pin "1") (pinfunction "1_1") (pintype "passive"))
      (node (ref "U26") (pin "2") (pinfunction "O_2") (pintype "output"))
      (node (ref "U26") (pin "3") (pinfunction "I_3") (pintype "input"))
    )
    (net (code "126") (name "Net-(U26B-O)") (class "Default")
      (node (ref "C47") (pin "2") (pinfunction "2_2") (pintype "passive"))
      (node (ref "R34") (pin "2") (pinfunction "2_2") (pintype "passive"))
      (node (ref "U26") (pin "4") (pinfunction "O_4") (pintype "output"))
      (node (ref "U26") (pin "5") (pinfunction "I_5") (pintype "input"))
    )
    (net (code "127") (name "Net-(U28-BIAS)") (class "Default")
      (node (ref "C55") (pin "2") (pinfunction "2_2") (pintype "passive"))
      (node (ref "R41") (pin "2") (pinfunction "2_2") (pintype "passive"))
      (node (ref "U28") (pin "13") (pinfunction "BIAS_13") (pintype "passive"))
      (node (ref "U29") (pin "7") (pinfunction "OUT_7") (pintype "output"))
    )
    (net (code "128") (name "Net-(U28-BIAS+)") (class "Default")
      (node (ref "C64") (pin "+") (pinfunction "+_+") (pintype "passive"))
      (node (ref "U28") (pin "15") (pinfunction "BIAS+_15") (pintype "passive"))
      (node (ref "U29") (pin "5") (pinfunction "+IN_5") (pintype "input"))
    )
    (net (code "129") (name "Net-(U28-BIAS-)") (class "Default")
      (node (ref "C55") (pin "1") (pinfunction "1_1") (pintype "passive"))
      (node (ref "U28") (pin "14") (pinfunction "BIAS-_14") (pintype "passive"))
      (node (ref "U29") (pin "6") (pinfunction "-IN_6") (pintype "input"))
    )
    (net (code "130") (name "Net-(U28-BUFF)") (class "Default")
      (node (ref "U28") (pin "12") (pinfunction "BUFF_12") (pintype "passive"))
      (node (ref "U29") (pin "3") (pinfunction "+IN_3") (pintype "input"))
    )
    (net (code "131") (name "Net-(U28-CH1)") (class "Default")
      (node (ref "C51") (pin "1") (pinfunction "1_1") (pintype "passive"))
      (node (ref "C53") (pin "-") (pinfunction "-_-") (pintype "passive"))
      (node (ref "U28") (pin "9") (pinfunction "CH1_9") (pintype "passive"))
    )
    (net (code "132") (name "Net-(U28-CH2)") (class "Default")
      (node (ref "C56") (pin "1") (pinfunction "1_1") (pintype "passive"))
      (node (ref "C57") (pin "-") (pinfunction "-_-") (pintype "passive"))
      (node (ref "U28") (pin "10") (pinfunction "CH2_10") (pintype "passive"))
    )
    (net (code "133") (name "Net-(U28-COM)") (class "Default")
      (node (ref "R43") (pin "2") (pinfunction "2_2") (pintype "passive"))
      (node (ref "U28") (pin "11") (pinfunction "COM_11") (pintype "passive"))
    )
    (net (code "134") (name "Net-(U29A--IN)") (class "Default")
      (node (ref "R43") (pin "1") (pinfunction "1_1") (pintype "passive"))
      (node (ref "U29") (pin "1") (pinfunction "OUT_1") (pintype "output"))
      (node (ref "U29") (pin "2") (pinfunction "-IN_2") (pintype "input"))
    )
    (net (code "135") (name "Net-(U29C-+IN)") (class "Default")
      (node (ref "C67") (pin "+") (pinfunction "+_+") (pintype "passive"))
      (node (ref "R55") (pin "1") (pinfunction "1_1") (pintype "passive"))
      (node (ref "R60") (pin "2") (pinfunction "2_2") (pintype "passive"))
      (node (ref "U29") (pin "10") (pinfunction "+IN_10") (pintype "input"))
    )
    (net (code "136") (name "Net-(U29D--IN)") (class "Default")
      (node (ref "C67") (pin "-") (pinfunction "-_-") (pintype "passive"))
      (node (ref "R59") (pin "2") (pinfunction "2_2") (pintype "passive"))
      (node (ref "U29") (pin "13") (pinfunction "-IN_13") (pintype "input"))
      (node (ref "U29") (pin "14") (pinfunction "OUT_14") (pintype "output"))
    )
    (net (code "137") (name "Net-(U30-CNTL)") (class "Default")
      (node (ref "C66") (pin "+") (pinfunction "+_+") (pintype "passive"))
      (node (ref "C97") (pin "2") (pinfunction "2_2") (pintype "passive"))
      (node (ref "R87") (pin "1") (pinfunction "1_1") (pintype "passive"))
      (node (ref "U30") (pin "2") (pinfunction "CNTL_2") (pintype "passive"))
    )
    (net (code "138") (name "Net-(U30-ROLOFF)") (class "Default")
      (node (ref "C76") (pin "1") (pinfunction "1_1") (pintype "passive"))
      (node (ref "U30") (pin "5") (pinfunction "ROLOFF_5") (pintype "passive"))
    )
    (net (code "139") (name "Net-(U30-VIN)") (class "Default")
      (node (ref "C68") (pin "-") (pinfunction "-_-") (pintype "passive"))
      (node (ref "U30") (pin "1") (pinfunction "VIN_1") (pintype "bidirectional"))
    )
    (net (code "140") (name "Net-(U30-VO)") (class "Default")
      (node (ref "R71") (pin "1") (pinfunction "1_1") (pintype "passive"))
      (node (ref "U30") (pin "7") (pinfunction "VO_7") (pintype "output"))
    )
    (net (code "141") (name "Net-(U31-BS-I)") (class "Default")
      (node (ref "C86") (pin "+") (pinfunction "+_+") (pintype "passive"))
      (node (ref "U31") (pin "9") (pinfunction "BS-I_9") (pintype "passive"))
    )
    (net (code "142") (name "Net-(U31-BS-M)") (class "Default")
      (node (ref "C87") (pin "+") (pinfunction "+_+") (pintype "passive"))
      (node (ref "U31") (pin "12") (pinfunction "BS-M_12") (pintype "output"))
    )
    (net (code "143") (name "Net-(U31-BYPASS)") (class "Default")
      (node (ref "C84") (pin "+") (pinfunction "+_+") (pintype "passive"))
      (node (ref "R92") (pin "2") (pinfunction "2_2") (pintype "passive"))
      (node (ref "U31") (pin "5") (pinfunction "BYPASS_5") (pintype "passive"))
    )
    (net (code "144") (name "Net-(U31-FEEDBACK)") (class "Default")
      (node (ref "C83") (pin "+") (pinfunction "+_+") (pintype "passive"))
      (node (ref "U31") (pin "4") (pinfunction "FEEDBACK_4") (pintype "passive"))
    )
    (net (code "145") (name "Net-(U31-IN)") (class "Default")
      (node (ref "C81") (pin "-") (pinfunction "-_-") (pintype "passive"))
      (node (ref "R92") (pin "1") (pinfunction "1_1") (pintype "passive"))
      (node (ref "U31") (pin "1") (pinfunction "IN_1") (pintype "passive"))
    )
    (net (code "146") (name "Net-(U31-MUTE)") (class "Default")
      (node (ref "C80") (pin "+") (pinfunction "+_+") (pintype "passive"))
      (node (ref "U31") (pin "6") (pinfunction "MUTE_6") (pintype "passive"))
    )
    (net (code "147") (name "Net-(U31-OUT(I))") (class "Default")
      (node (ref "C86") (pin "-") (pinfunction "-_-") (pintype "passive"))
      (node (ref "C90") (pin "2") (pinfunction "2_2") (pintype "passive"))
      (node (ref "C92") (pin "2") (pinfunction "2_2") (pintype "passive"))
      (node (ref "P7") (pin "3") (pinfunction "3_3") (pintype "passive"))
      (node (ref "P7") (pin "4") (pinfunction "4_4") (pintype "passive"))
      (node (ref "U31") (pin "8") (pinfunction "OUT(I)_8") (pintype "output"))
    )
    (net (code "148") (name "Net-(U31-OUT(M))") (class "Default")
      (node (ref "C87") (pin "-") (pinfunction "-_-") (pintype "passive"))
      (node (ref "C91") (pin "2") (pinfunction "2_2") (pintype "passive"))
      (node (ref "C92") (pin "1") (pinfunction "1_1") (pintype "passive"))
      (node (ref "P7") (pin "1") (pinfunction "1_1") (pintype "passive"))
      (node (ref "P7") (pin "2") (pinfunction "2_2") (pintype "passive"))
      (node (ref "U31") (pin "10") (pinfunction "OUT(M)_10") (pintype "passive"))
    )
    (net (code "149") (name "Net-(U32A-+IN)") (class "Default")
      (node (ref "C46") (pin "+") (pinfunction "+_+") (pintype "passive"))
      (node (ref "R33") (pin "2") (pinfunction "2_2") (pintype "passive"))
      (node (ref "R48") (pin "1") (pinfunction "1_1") (pintype "passive"))
      (node (ref "U32") (pin "3") (pinfunction "+IN_3") (pintype "input"))
    )
    (net (code "150") (name "Net-(U32A--IN)") (class "Default")
      (node (ref "R39") (pin "2") (pinfunction "2_2") (pintype "passive"))
      (node (ref "U32") (pin "1") (pinfunction "OUT_1") (pintype "output"))
      (node (ref "U32") (pin "2") (pinfunction "-IN_2") (pintype "input"))
    )
    (net (code "151") (name "Net-(U32B-+IN)") (class "Default")
      (node (ref "C48") (pin "1") (pinfunction "1_1") (pintype "passive"))
      (node (ref "R36") (pin "1") (pinfunction "1_1") (pintype "passive"))
      (node (ref "U32") (pin "5") (pinfunction "+IN_5") (pintype "input"))
    )
    (net (code "152") (name "Net-(U32C--IN)") (class "Default")
      (node (ref "C59") (pin "2") (pinfunction "2_2") (pintype "passive"))
      (node (ref "R46") (pin "1") (pinfunction "1_1") (pintype "passive"))
      (node (ref "U32") (pin "9") (pinfunction "-IN_9") (pintype "input"))
    )
    (net (code "153") (name "Net-(U32C-OUT)") (class "Default")
      (node (ref "C59") (pin "1") (pinfunction "1_1") (pintype "passive"))
      (node (ref "R45") (pin "1") (pinfunction "1_1") (pintype "passive"))
      (node (ref "R78") (pin "2") (pinfunction "2_2") (pintype "passive"))
      (node (ref "U32") (pin "8") (pinfunction "OUT_8") (pintype "output"))
    )
    (net (code "154") (name "Net-(U32D-+IN)") (class "Default")
      (node (ref "C50") (pin "1") (pinfunction "1_1") (pintype "passive"))
      (node (ref "R38") (pin "1") (pinfunction "1_1") (pintype "passive"))
      (node (ref "U32") (pin "12") (pinfunction "+IN_12") (pintype "input"))
    )
    (net (code "155") (name "Net-(U32D--IN)") (class "Default")
      (node (ref "C52") (pin "1") (pinfunction "1_1") (pintype "passive"))
      (node (ref "R35") (pin "2") (pinfunction "2_2") (pintype "passive"))
      (node (ref "U32") (pin "13") (pinfunction "-IN_13") (pintype "input"))
      (node (ref "U32") (pin "14") (pinfunction "OUT_14") (pintype "output"))
    )
    (net (code "156") (name "Net-(U33A--IN)") (class "Default")
      (node (ref "C71") (pin "2") (pinfunction "2_2") (pintype "passive"))
      (node (ref "R64") (pin "1") (pinfunction "1_1") (pintype "passive"))
      (node (ref "U33") (pin "2") (pinfunction "-IN_2") (pintype "input"))
    )
    (net (code "157") (name "Net-(U33A-OUT)") (class "Default")
      (node (ref "C71") (pin "1") (pinfunction "1_1") (pintype "passive"))
      (node (ref "R63") (pin "1") (pinfunction "1_1") (pintype "passive"))
      (node (ref "R79") (pin "2") (pinfunction "2_2") (pintype "passive"))
      (node (ref "U33") (pin "1") (pinfunction "OUT_1") (pintype "output"))
    )
    (net (code "158") (name "Net-(U33B--IN)") (class "Default")
      (node (ref "C60") (pin "2") (pinfunction "2_2") (pintype "passive"))
      (node (ref "R52") (pin "1") (pinfunction "1_1") (pintype "passive"))
      (node (ref "U33") (pin "6") (pinfunction "-IN_6") (pintype "input"))
    )
    (net (code "159") (name "Net-(U33B-OUT)") (class "Default")
      (node (ref "C60") (pin "1") (pinfunction "1_1") (pintype "passive"))
      (node (ref "R51") (pin "1") (pinfunction "1_1") (pintype "passive"))
      (node (ref "R77") (pin "2") (pinfunction "2_2") (pintype "passive"))
      (node (ref "U33") (pin "7") (pinfunction "OUT_7") (pintype "output"))
    )
    (net (code "160") (name "Net-(U33D--IN)") (class "Default")
      (node (ref "C96") (pin "1") (pinfunction "1_1") (pintype "passive"))
      (node (ref "R77") (pin "1") (pinfunction "1_1") (pintype "passive"))
      (node (ref "R78") (pin "1") (pinfunction "1_1") (pintype "passive"))
      (node (ref "R79") (pin "1") (pinfunction "1_1") (pintype "passive"))
      (node (ref "R81") (pin "1") (pinfunction "1_1") (pintype "passive"))
      (node (ref "R88") (pin "2") (pinfunction "2_2") (pintype "passive"))
      (node (ref "U33") (pin "13") (pinfunction "-IN_13") (pintype "input"))
    )
    (net (code "161") (name "Net-(U33D-OUT)") (class "Default")
      (node (ref "C68") (pin "+") (pinfunction "+_+") (pintype "passive"))
      (node (ref "C96") (pin "2") (pinfunction "2_2") (pintype "passive"))
      (node (ref "R88") (pin "1") (pinfunction "1_1") (pintype "passive"))
      (node (ref "U33") (pin "14") (pinfunction "OUT_14") (pintype "output"))
    )
    (net (code "162") (name "PCM-A0") (class "Default")
      (node (ref "U1") (pin "18") (pinfunction "A0_18") (pintype "passive"))
      (node (ref "U12") (pin "12") (pinfunction "A0_12") (pintype "passive"))
      (node (ref "U13") (pin "12") (pinfunction "A0_12") (pintype "passive"))
    )
    (net (code "163") (name "PCM-A1") (class "Default")
      (node (ref "U1") (pin "19") (pinfunction "A1_19") (pintype "passive"))
      (node (ref "U12") (pin "11") (pinfunction "A1_11") (pintype "passive"))
      (node (ref "U13") (pin "11") (pinfunction "A1_11") (pintype "passive"))
    )
    (net (code "164") (name "PCM-A2") (class "Default")
      (node (ref "U1") (pin "20") (pinfunction "A2_20") (pintype "passive"))
      (node (ref "U12") (pin "10") (pinfunction "A2_10") (pintype "passive"))
      (node (ref "U13") (pin "10") (pinfunction "A2_10") (pintype "passive"))
    )
    (net (code "165") (name "PCM-A3") (class "Default")
      (node (ref "U1") (pin "21") (pinfunction "A3_21") (pintype "passive"))
      (node (ref "U12") (pin "9") (pinfunction "A3_9") (pintype "passive"))
      (node (ref "U13") (pin "9") (pinfunction "A3_9") (pintype "passive"))
    )
    (net (code "166") (name "PCM-A4") (class "Default")
      (node (ref "U1") (pin "22") (pinfunction "A4_22") (pintype "passive"))
      (node (ref "U12") (pin "8") (pinfunction "A4_8") (pintype "passive"))
      (node (ref "U13") (pin "8") (pinfunction "A4_8") (pintype "passive"))
    )
    (net (code "167") (name "PCM-A5") (class "Default")
      (node (ref "U1") (pin "23") (pinfunction "A5_23") (pintype "passive"))
      (node (ref "U12") (pin "7") (pinfunction "A5_7") (pintype "passive"))
      (node (ref "U13") (pin "7") (pinfunction "A5_7") (pintype "passive"))
    )
    (net (code "168") (name "PCM-A6") (class "Default")
      (node (ref "U1") (pin "24") (pinfunction "A6_24") (pintype "passive"))
      (node (ref "U12") (pin "6") (pinfunction "A6_6") (pintype "passive"))
      (node (ref "U13") (pin "6") (pinfunction "A6_6") (pintype "passive"))
    )
    (net (code "169") (name "PCM-A7") (class "Default")
      (node (ref "U1") (pin "25") (pinfunction "A7_25") (pintype "passive"))
      (node (ref "U12") (pin "5") (pinfunction "A7_5") (pintype "passive"))
      (node (ref "U13") (pin "5") (pinfunction "A7_5") (pintype "passive"))
    )
    (net (code "170") (name "PCM-A8") (class "Default")
      (node (ref "U1") (pin "26") (pinfunction "A8_26") (pintype "passive"))
      (node (ref "U12") (pin "27") (pinfunction "A8_27") (pintype "passive"))
      (node (ref "U13") (pin "27") (pinfunction "A8_27") (pintype "passive"))
    )
    (net (code "171") (name "PCM-A9") (class "Default")
      (node (ref "U1") (pin "27") (pinfunction "A9_27") (pintype "passive"))
      (node (ref "U12") (pin "26") (pinfunction "A9_26") (pintype "passive"))
      (node (ref "U13") (pin "26") (pinfunction "A9_26") (pintype "passive"))
    )
    (net (code "172") (name "PCM-A10") (class "Default")
      (node (ref "U1") (pin "28") (pinfunction "A10_28") (pintype "passive"))
      (node (ref "U12") (pin "23") (pinfunction "A10_23") (pintype "passive"))
      (node (ref "U13") (pin "23") (pinfunction "A10_23") (pintype "passive"))
    )
    (net (code "173") (name "PCM-A11") (class "Default")
      (node (ref "U1") (pin "29") (pinfunction "A11_29") (pintype "passive"))
      (node (ref "U12") (pin "25") (pinfunction "A11_25") (pintype "passive"))
      (node (ref "U13") (pin "25") (pinfunction "A11_25") (pintype "passive"))
    )
    (net (code "174") (name "PCM-A12") (class "Default")
      (node (ref "U1") (pin "30") (pinfunction "A12_30") (pintype "passive"))
      (node (ref "U12") (pin "4") (pinfunction "A12_4") (pintype "passive"))
      (node (ref "U13") (pin "4") (pinfunction "A12_4") (pintype "passive"))
    )
    (net (code "175") (name "PCM-A13") (class "Default")
      (node (ref "U1") (pin "31") (pinfunction "A13_31") (pintype "passive"))
      (node (ref "U12") (pin "28") (pinfunction "A13_28") (pintype "passive"))
      (node (ref "U13") (pin "28") (pinfunction "A13_28") (pintype "passive"))
    )
    (net (code "176") (name "PCM-A14") (class "Default")
      (node (ref "U1") (pin "32") (pinfunction "A14_32") (pintype "passive"))
      (node (ref "U12") (pin "29") (pinfunction "A14_29") (pintype "passive"))
      (node (ref "U13") (pin "29") (pinfunction "A14_29") (pintype "passive"))
    )
    (net (code "177") (name "PCM-A15") (class "Default")
      (node (ref "U1") (pin "33") (pinfunction "A15_33") (pintype "passive"))
      (node (ref "U12") (pin "3") (pinfunction "A15_3") (pintype "passive"))
      (node (ref "U13") (pin "3") (pinfunction "A15_3") (pintype "passive"))
    )
    (net (code "178") (name "PCM-A16") (class "Default")
      (node (ref "U1") (pin "34") (pinfunction "A16_34") (pintype "passive"))
      (node (ref "U12") (pin "2") (pinfunction "A16_2") (pintype "passive"))
      (node (ref "U13") (pin "2") (pinfunction "A16_2") (pintype "passive"))
    )
    (net (code "179") (name "PCM-A17") (class "Default")
      (node (ref "U1") (pin "35") (pinfunction "A17_35") (pintype "passive"))
      (node (ref "U18") (pin "4") (pinfunction "4-IN_4") (pintype "passive"))
      (node (ref "U26") (pin "13") (pinfunction "I_13") (pintype "input"))
    )
    (net (code "180") (name "PCM-BS") (class "Default")
      (node (ref "U17") (pin "9") (pinfunction "CLK_9") (pintype "input"))
      (node (ref "U8") (pin "10") (pinfunction "Y5_10") (pintype "output"))
    )
    (net (code "181") (name "PCM-D0") (class "Default")
      (node (ref "U1") (pin "9") (pinfunction "SD0_9") (pintype "passive"))
      (node (ref "U12") (pin "13") (pinfunction "D0_13") (pintype "passive"))
      (node (ref "U13") (pin "13") (pinfunction "D0_13") (pintype "passive"))
    )
    (net (code "182") (name "PCM-D1") (class "Default")
      (node (ref "U1") (pin "10") (pinfunction "SD1_10") (pintype "passive"))
      (node (ref "U12") (pin "14") (pinfunction "D1_14") (pintype "passive"))
      (node (ref "U13") (pin "14") (pinfunction "D1_14") (pintype "passive"))
    )
    (net (code "183") (name "PCM-D2") (class "Default")
      (node (ref "U1") (pin "11") (pinfunction "SD2_11") (pintype "passive"))
      (node (ref "U12") (pin "15") (pinfunction "D2_15") (pintype "passive"))
      (node (ref "U13") (pin "15") (pinfunction "D2_15") (pintype "passive"))
    )
    (net (code "184") (name "PCM-D3") (class "Default")
      (node (ref "U1") (pin "12") (pinfunction "SD3_12") (pintype "passive"))
      (node (ref "U12") (pin "17") (pinfunction "D3_17") (pintype "passive"))
      (node (ref "U13") (pin "17") (pinfunction "D3_17") (pintype "passive"))
      (node (ref "U13") (pin "18") (pinfunction "D4_18") (pintype "passive"))
    )
    (net (code "185") (name "PCM-D4") (class "Default")
      (node (ref "U1") (pin "13") (pinfunction "SD4_13") (pintype "passive"))
      (node (ref "U12") (pin "18") (pinfunction "D4_18") (pintype "passive"))
    )
    (net (code "186") (name "PCM-D5") (class "Default")
      (node (ref "U1") (pin "14") (pinfunction "SD5_14") (pintype "passive"))
      (node (ref "U12") (pin "19") (pinfunction "D5_19") (pintype "passive"))
      (node (ref "U13") (pin "19") (pinfunction "D5_19") (pintype "passive"))
    )
    (net (code "187") (name "PCM-D6") (class "Default")
      (node (ref "U1") (pin "15") (pinfunction "SD6_15") (pintype "passive"))
      (node (ref "U12") (pin "20") (pinfunction "D6_20") (pintype "passive"))
      (node (ref "U13") (pin "20") (pinfunction "D6_20") (pintype "passive"))
    )
    (net (code "188") (name "PCM-D7") (class "Default")
      (node (ref "U1") (pin "16") (pinfunction "SD7_16") (pintype "passive"))
      (node (ref "U12") (pin "21") (pinfunction "D7_21") (pintype "passive"))
      (node (ref "U13") (pin "21") (pinfunction "D7_21") (pintype "passive"))
    )
    (net (code "189") (name "PCM-OUT") (class "Default")
      (node (ref "C58") (pin "1") (pinfunction "1_1") (pintype "passive"))
      (node (ref "R81") (pin "2") (pinfunction "2_2") (pintype "passive"))
      (node (ref "U32") (pin "6") (pinfunction "-IN_6") (pintype "input"))
      (node (ref "U32") (pin "7") (pinfunction "OUT_7") (pintype "output"))
    )
    (net (code "190") (name "RA17-0") (class "Default")
      (node (ref "U12") (pin "30") (pinfunction "A17_30") (pintype "passive"))
      (node (ref "U18") (pin "17") (pinfunction "I/O-17_17") (pintype "passive"))
    )
    (net (code "191") (name "RA17-1") (class "Default")
      (node (ref "U13") (pin "30") (pinfunction "A17_30") (pintype "passive"))
      (node (ref "U18") (pin "14") (pinfunction "I/O-14_14") (pintype "passive"))
    )
    (net (code "192") (name "RA18-0") (class "Default")
      (node (ref "U12") (pin "31") (pinfunction "A18_31") (pintype "passive"))
      (node (ref "U18") (pin "12") (pinfunction "OUT-12_12") (pintype "passive"))
    )
    (net (code "193") (name "RA18-1") (class "Default")
      (node (ref "U13") (pin "31") (pinfunction "A18_31") (pintype "passive"))
      (node (ref "U18") (pin "13") (pinfunction "I/O-13_13") (pintype "passive"))
    )
    (net (code "194") (name "RD-LATCH") (class "Default")
      (node (ref "U10") (pin "12") (pinfunction "~{EN}_12") (pintype "bidirectional"))
      (node (ref "U23") (pin "10") (pinfunction "PRE_10") (pintype "input"))
      (node (ref "U24") (pin "7") (pinfunction "INB_7") (pintype "input"))
      (node (ref "U6") (pin "12") (pinfunction "~{EN}_12") (pintype "bidirectional"))
      (node (ref "U8") (pin "11") (pinfunction "Y4_11") (pintype "output"))
    )
    (net (code "195") (name "RESET") (class "Default")
      (node (ref "R3") (pin "1") (pinfunction "1_1") (pintype "passive"))
      (node (ref "U1") (pin "8") (pinfunction "~{RESET}_8") (pintype "passive"))
      (node (ref "U14") (pin "3") (pinfunction "~{RESET}_3") (pintype "passive"))
      (node (ref "U19") (pin "12") (pinfunction "O_12") (pintype "output"))
      (node (ref "U28") (pin "7") (pinfunction "~{RESET}_7") (pintype "passive"))
      (node (ref "U4") (pin "37") (pinfunction "~{RESET}_37") (pintype "passive"))
    )
    (net (code "196") (name "R{slash}W") (class "Default")
      (node (ref "U18") (pin "9") (pinfunction "9-IN_9") (pintype "passive"))
      (node (ref "U4") (pin "32") (pinfunction "R/W_32") (pintype "passive"))
    )
    (net (code "197") (name "SNDVIDRD") (class "Default")
      (node (ref "C105") (pin "2") (pinfunction "2_2") (pintype "passive"))
      (node (ref "R86") (pin "1") (pinfunction "1_1") (pintype "passive"))
      (node (ref "R95") (pin "1") (pinfunction "1_1") (pintype "passive"))
      (node (ref "U25") (pin "10") (pinfunction "INC_10") (pintype "bidirectional"))
    )
    (net (code "198") (name "SND_DAT0") (class "Default")
      (node (ref "C35") (pin "1") (pinfunction "1_1") (pintype "passive"))
      (node (ref "P1") (pin "3") (pinfunction "3_3") (pintype "passive"))
      (node (ref "R11") (pin "2") (pinfunction "2_2") (pintype "passive"))
    )
    (net (code "199") (name "SND_DAT1") (class "Default")
      (node (ref "C37") (pin "1") (pinfunction "1_1") (pintype "passive"))
      (node (ref "P1") (pin "4") (pinfunction "4_4") (pintype "passive"))
      (node (ref "R13") (pin "2") (pinfunction "2_2") (pintype "passive"))
    )
    (net (code "200") (name "SND_DAT2") (class "Default")
      (node (ref "C38") (pin "1") (pinfunction "1_1") (pintype "passive"))
      (node (ref "P1") (pin "5") (pinfunction "5_5") (pintype "passive"))
      (node (ref "R14") (pin "2") (pinfunction "2_2") (pintype "passive"))
    )
    (net (code "201") (name "SND_DAT3") (class "Default")
      (node (ref "C36") (pin "1") (pinfunction "1_1") (pintype "passive"))
      (node (ref "P1") (pin "6") (pinfunction "6_6") (pintype "passive"))
      (node (ref "R12") (pin "2") (pinfunction "2_2") (pintype "passive"))
    )
    (net (code "202") (name "SND_DAT4") (class "Default")
      (node (ref "C39") (pin "1") (pinfunction "1_1") (pintype "passive"))
      (node (ref "P1") (pin "7") (pinfunction "7_7") (pintype "passive"))
      (node (ref "R15") (pin "2") (pinfunction "2_2") (pintype "passive"))
    )
    (net (code "203") (name "SND_DAT5") (class "Default")
      (node (ref "C40") (pin "1") (pinfunction "1_1") (pintype "passive"))
      (node (ref "P1") (pin "8") (pinfunction "8_8") (pintype "passive"))
      (node (ref "R16") (pin "2") (pinfunction "2_2") (pintype "passive"))
    )
    (net (code "204") (name "SND_DAT6") (class "Default")
      (node (ref "C41") (pin "1") (pinfunction "1_1") (pintype "passive"))
      (node (ref "P1") (pin "9") (pinfunction "9_9") (pintype "passive"))
      (node (ref "R17") (pin "2") (pinfunction "2_2") (pintype "passive"))
    )
    (net (code "205") (name "SND_DAT7") (class "Default")
      (node (ref "C42") (pin "1") (pinfunction "1_1") (pintype "passive"))
      (node (ref "P1") (pin "10") (pinfunction "10_10") (pintype "passive"))
      (node (ref "R18") (pin "2") (pinfunction "2_2") (pintype "passive"))
    )
    (net (code "206") (name "SND_DAT8") (class "Default")
      (node (ref "C107") (pin "1") (pinfunction "1_1") (pintype "passive"))
      (node (ref "R84") (pin "1") (pinfunction "1_1") (pintype "passive"))
      (node (ref "R94") (pin "1") (pinfunction "1_1") (pintype "passive"))
      (node (ref "U25") (pin "2") (pinfunction "INA_2") (pintype "bidirectional"))
    )
    (net (code "207") (name "SND_DAV") (class "Default")
      (node (ref "C45") (pin "1") (pinfunction "1_1") (pintype "passive"))
      (node (ref "P1") (pin "19") (pinfunction "19_19") (pintype "passive"))
      (node (ref "R21") (pin "2") (pinfunction "2_2") (pintype "passive"))
    )
    (net (code "208") (name "SND_RDY") (class "Default")
      (node (ref "C43") (pin "1") (pinfunction "1_1") (pintype "passive"))
      (node (ref "P1") (pin "11") (pinfunction "11_11") (pintype "passive"))
      (node (ref "R19") (pin "2") (pinfunction "2_2") (pintype "passive"))
    )
    (net (code "209") (name "SOFT_RES") (class "Default")
      (node (ref "U19") (pin "13") (pinfunction "I2_13") (pintype "input"))
      (node (ref "U25") (pin "3") (pinfunction "OUTA_3") (pintype "bidirectional"))
    )
    (net (code "210") (name "VIDPWRON") (class "Default")
      (node (ref "U19") (pin "2") (pinfunction "I1_2") (pintype "input"))
      (node (ref "U25") (pin "5") (pinfunction "OUTB_5") (pintype "bidirectional"))
    )
    (net (code "211") (name "VIDSNDRD") (class "Default")
      (node (ref "U11") (pin "12") (pinfunction "~{EN}_12") (pintype "bidirectional"))
      (node (ref "U25") (pin "11") (pinfunction "OUTC_11") (pintype "bidirectional"))
      (node (ref "U7") (pin "12") (pinfunction "~{EN}_12") (pintype "bidirectional"))
      (node (ref "U9") (pin "13") (pinfunction "CLR_13") (pintype "input"))
    )
    (net (code "212") (name "WR-LATCH") (class "Default")
      (node (ref "U5") (pin "11") (pinfunction "CLK_11") (pintype "input"))
      (node (ref "U8") (pin "7") (pinfunction "Y7_7") (pintype "output"))
      (node (ref "U9") (pin "11") (pinfunction "CLK_11") (pintype "input"))
    )
    (net (code "213") (name "YAM") (class "Default")
      (node (ref "U14") (pin "7") (pinfunction "~{CS}_7") (pintype "passive"))
      (node (ref "U8") (pin "14") (pinfunction "Y1_14") (pintype "output"))
    )
    (net (code "214") (name "YAM1-OUT") (class "Default")
      (node (ref "C53") (pin "+") (pinfunction "+_+") (pintype "passive"))
      (node (ref "R40") (pin "2") (pinfunction "2_2") (pintype "passive"))
    )
    (net (code "215") (name "YAM2-OUT") (class "Default")
      (node (ref "C57") (pin "+") (pinfunction "+_+") (pintype "passive"))
      (node (ref "R44") (pin "2") (pinfunction "2_2") (pintype "passive"))
    )
    (net (code "216") (name "unconnected-(P1-Pad2)") (class "Default")
      (node (ref "P1") (pin "2") (pinfunction "2_2") (pintype "passive"))
    )
    (net (code "217") (name "unconnected-(P1-Pad12)") (class "Default")
      (node (ref "P1") (pin "12") (pinfunction "12_12") (pintype "passive"))
    )
    (net (code "218") (name "unconnected-(P1-Pad14)") (class "Default")
      (node (ref "P1") (pin "14") (pinfunction "14_14") (pintype "passive"))
    )
    (net (code "219") (name "unconnected-(P1-Pad20)") (class "Default")
      (node (ref "P1") (pin "20") (pinfunction "20_20") (pintype "passive"))
    )
    (net (code "220") (name "unconnected-(P6-Pad3)") (class "Default")
      (node (ref "P6") (pin "3") (pinfunction "3_3") (pintype "passive"))
    )
    (net (code "221") (name "unconnected-(P6-Pad4)") (class "Default")
      (node (ref "P6") (pin "4") (pinfunction "4_4") (pintype "passive"))
    )
    (net (code "222") (name "unconnected-(U1-~{XTAL}-Pad6)") (class "Default")
      (node (ref "U1") (pin "6") (pinfunction "~{XTAL}_6") (pintype "passive"))
    )
    (net (code "223") (name "unconnected-(U4-AVMA-Pad36)") (class "Default")
      (node (ref "U4") (pin "36") (pinfunction "AVMA_36") (pintype "passive"))
    )
    (net (code "224") (name "unconnected-(U4-BA-Pad6)") (class "Default")
      (node (ref "U4") (pin "6") (pinfunction "BA_6") (pintype "passive"))
    )
    (net (code "225") (name "unconnected-(U4-BS-Pad5)") (class "Default")
      (node (ref "U4") (pin "5") (pinfunction "BS_5") (pintype "passive"))
    )
    (net (code "226") (name "unconnected-(U4-BUSY-Pad33)") (class "Default")
      (node (ref "U4") (pin "33") (pinfunction "BUSY_33") (pintype "passive"))
    )
    (net (code "227") (name "unconnected-(U4-LIC-Pad38)") (class "Default")
      (node (ref "U4") (pin "38") (pinfunction "LIC_38") (pintype "passive"))
    )
    (net (code "228") (name "unconnected-(U4-VCC-Pad7)") (class "Default")
      (node (ref "U4") (pin "7") (pinfunction "VCC_7") (pintype "passive"))
    )
    (net (code "229") (name "unconnected-(U7-~{OUTA}-Pad3)") (class "Default")
      (node (ref "U7") (pin "3") (pinfunction "~{OUTA}_3") (pintype "bidirectional"))
    )
    (net (code "230") (name "unconnected-(U7-~{OUTB}-Pad5)") (class "Default")
      (node (ref "U7") (pin "5") (pinfunction "~{OUTB}_5") (pintype "bidirectional"))
    )
    (net (code "231") (name "unconnected-(U7-~{OUTC}-Pad11)") (class "Default")
      (node (ref "U7") (pin "11") (pinfunction "~{OUTC}_11") (pintype "bidirectional"))
    )
    (net (code "232") (name "unconnected-(U7-~{OUTD}-Pad13)") (class "Default")
      (node (ref "U7") (pin "13") (pinfunction "~{OUTD}_13") (pintype "bidirectional"))
    )
    (net (code "233") (name "unconnected-(U8A-Y6-Pad9)") (class "Default")
      (node (ref "U8") (pin "9") (pinfunction "Y6_9") (pintype "output"))
    )
    (net (code "234") (name "unconnected-(U9B-~{Q}-Pad8)") (class "Default")
      (node (ref "U9") (pin "8") (pinfunction "~{Q}_8") (pintype "output"))
    )
    (net (code "235") (name "unconnected-(U11-~{OUTA}-Pad3)") (class "Default")
      (node (ref "U11") (pin "3") (pinfunction "~{OUTA}_3") (pintype "bidirectional"))
    )
    (net (code "236") (name "unconnected-(U11-~{OUTB}-Pad5)") (class "Default")
      (node (ref "U11") (pin "5") (pinfunction "~{OUTB}_5") (pintype "bidirectional"))
    )
    (net (code "237") (name "unconnected-(U11-~{OUTC}-Pad11)") (class "Default")
      (node (ref "U11") (pin "11") (pinfunction "~{OUTC}_11") (pintype "bidirectional"))
    )
    (net (code "238") (name "unconnected-(U11-~{OUTD}-Pad13)") (class "Default")
      (node (ref "U11") (pin "13") (pinfunction "~{OUTD}_13") (pintype "bidirectional"))
    )
    (net (code "239") (name "unconnected-(U14-CT1-Pad8)") (class "Default")
      (node (ref "U14") (pin "8") (pinfunction "CT1_8") (pintype "passive"))
    )
    (net (code "240") (name "unconnected-(U14-CT2-Pad9)") (class "Default")
      (node (ref "U14") (pin "9") (pinfunction "CT2_9") (pintype "passive"))
    )
    (net (code "241") (name "unconnected-(U15-RFB-Pad16)") (class "Default")
      (node (ref "U15") (pin "16") (pinfunction "RFB_16") (pintype "passive"))
    )
    (net (code "242") (name "unconnected-(U16A-5Q-Pad12)") (class "Default")
      (node (ref "U16") (pin "12") (pinfunction "5Q_12") (pintype "tri_state"))
    )
    (net (code "243") (name "unconnected-(U16A-6Q-Pad15)") (class "Default")
      (node (ref "U16") (pin "15") (pinfunction "6Q_15") (pintype "tri_state"))
    )
    (net (code "244") (name "unconnected-(U16A-7Q-Pad16)") (class "Default")
      (node (ref "U16") (pin "16") (pinfunction "7Q_16") (pintype "tri_state"))
    )
    (net (code "245") (name "unconnected-(U16A-8Q-Pad19)") (class "Default")
      (node (ref "U16") (pin "19") (pinfunction "8Q_19") (pintype "tri_state"))
    )
    (net (code "246") (name "unconnected-(U17A-Q1-Pad2)") (class "Default")
      (node (ref "U17") (pin "2") (pinfunction "Q1_2") (pintype "output"))
    )
    (net (code "247") (name "unconnected-(U17A-Q4-Pad10)") (class "Default")
      (node (ref "U17") (pin "10") (pinfunction "Q4_10") (pintype "output"))
    )
    (net (code "248") (name "unconnected-(U17A-Q5-Pad12)") (class "Default")
      (node (ref "U17") (pin "12") (pinfunction "Q5_12") (pintype "output"))
    )
    (net (code "249") (name "unconnected-(U18-I{slash}O-16-Pad16)") (class "Default")
      (node (ref "U18") (pin "16") (pinfunction "I/O-16_16") (pintype "passive"))
    )
    (net (code "250") (name "unconnected-(U20B-Y2-Pad10)") (class "Default")
      (node (ref "U20") (pin "10") (pinfunction "Y2_10") (pintype "output"))
    )
    (net (code "251") (name "unconnected-(U20B-Y3-Pad9)") (class "Default")
      (node (ref "U20") (pin "9") (pinfunction "Y3_9") (pintype "output"))
    )
    (net (code "252") (name "unconnected-(U22B-Q-Pad9)") (class "Default")
      (node (ref "U22") (pin "9") (pinfunction "Q_9") (pintype "output"))
    )
    (net (code "253") (name "unconnected-(U22B-~{Q}-Pad8)") (class "Default")
      (node (ref "U22") (pin "8") (pinfunction "~{Q}_8") (pintype "output"))
    )
    (net (code "254") (name "unconnected-(U23B-~{Q}-Pad8)") (class "Default")
      (node (ref "U23") (pin "8") (pinfunction "~{Q}_8") (pintype "output"))
    )
    (net (code "255") (name "unconnected-(U24-OUTC-Pad10)") (class "Default")
      (node (ref "U24") (pin "10") (pinfunction "OUTC_10") (pintype "bidirectional"))
    )
    (net (code "256") (name "unconnected-(U24-~{OUTA}-Pad3)") (class "Default")
      (node (ref "U24") (pin "3") (pinfunction "~{OUTA}_3") (pintype "bidirectional"))
    )
    (net (code "257") (name "unconnected-(U24-~{OUTB}-Pad5)") (class "Default")
      (node (ref "U24") (pin "5") (pinfunction "~{OUTB}_5") (pintype "bidirectional"))
    )
    (net (code "258") (name "unconnected-(U24-~{OUTC}-Pad11)") (class "Default")
      (node (ref "U24") (pin "11") (pinfunction "~{OUTC}_11") (pintype "bidirectional"))
    )
    (net (code "259") (name "unconnected-(U24-~{OUTD}-Pad13)") (class "Default")
      (node (ref "U24") (pin "13") (pinfunction "~{OUTD}_13") (pintype "bidirectional"))
    )
    (net (code "260") (name "unconnected-(U31-NC-Pad2)") (class "Default")
      (node (ref "U31") (pin "2") (pinfunction "NC_2") (pintype "no_connect"))
    )
    (net (code "261") (name "unconnected-(Y2-EN-Pad1)") (class "Default")
      (node (ref "Y2") (pin "1") (pinfunction "EN_1") (pintype "bidirectional"))
    )
    (net (code "262") (name "{slash}E") (class "Default")
      (node (ref "C62") (pin "1") (pinfunction "1_1") (pintype "passive"))
      (node (ref "R28") (pin "1") (pinfunction "1_1") (pintype "passive"))
      (node (ref "U18") (pin "5") (pinfunction "5-IN_5") (pintype "passive"))
      (node (ref "U22") (pin "6") (pinfunction "~{Q}_6") (pintype "output"))
      (node (ref "U23") (pin "2") (pinfunction "D_2") (pintype "input"))
    )
    (net (code "263") (name "{slash}EORQ") (class "Default")
      (node (ref "U18") (pin "15") (pinfunction "I/O-15_15") (pintype "passive"))
      (node (ref "U20") (pin "1") (pinfunction "G_1") (pintype "input"))
    )
    (net (code "264") (name "{slash}Q") (class "Default")
      (node (ref "U18") (pin "6") (pinfunction "6-IN_6") (pintype "passive"))
      (node (ref "U23") (pin "6") (pinfunction "~{Q}_6") (pintype "output"))
    )
    (net (code "265") (name "{slash}RD") (class "Default")
      (node (ref "U1") (pin "2") (pinfunction "~{RD}_2") (pintype "passive"))
      (node (ref "U14") (pin "6") (pinfunction "~{RD}_6") (pintype "passive"))
      (node (ref "U18") (pin "18") (pinfunction "I/O-18_18") (pintype "passive"))
      (node (ref "U2") (pin "22") (pinfunction "~{OE}_22") (pintype "input"))
    )
    (net (code "266") (name "{slash}WR") (class "Default")
      (node (ref "U1") (pin "3") (pinfunction "~{WR}_3") (pintype "passive"))
      (node (ref "U14") (pin "5") (pinfunction "~{WR}_5") (pintype "passive"))
      (node (ref "U15") (pin "13") (pinfunction "~{WR}_13") (pintype "input"))
      (node (ref "U18") (pin "19") (pinfunction "OUT-19_19") (pintype "passive"))
      (node (ref "U2") (pin "27") (pinfunction "~{WE}_27") (pintype "input"))
    )
  )
)
